# 03_-_28PINS_SCHEMATIC.net
KiCad netlist of a schematic drawn in Altium Designer
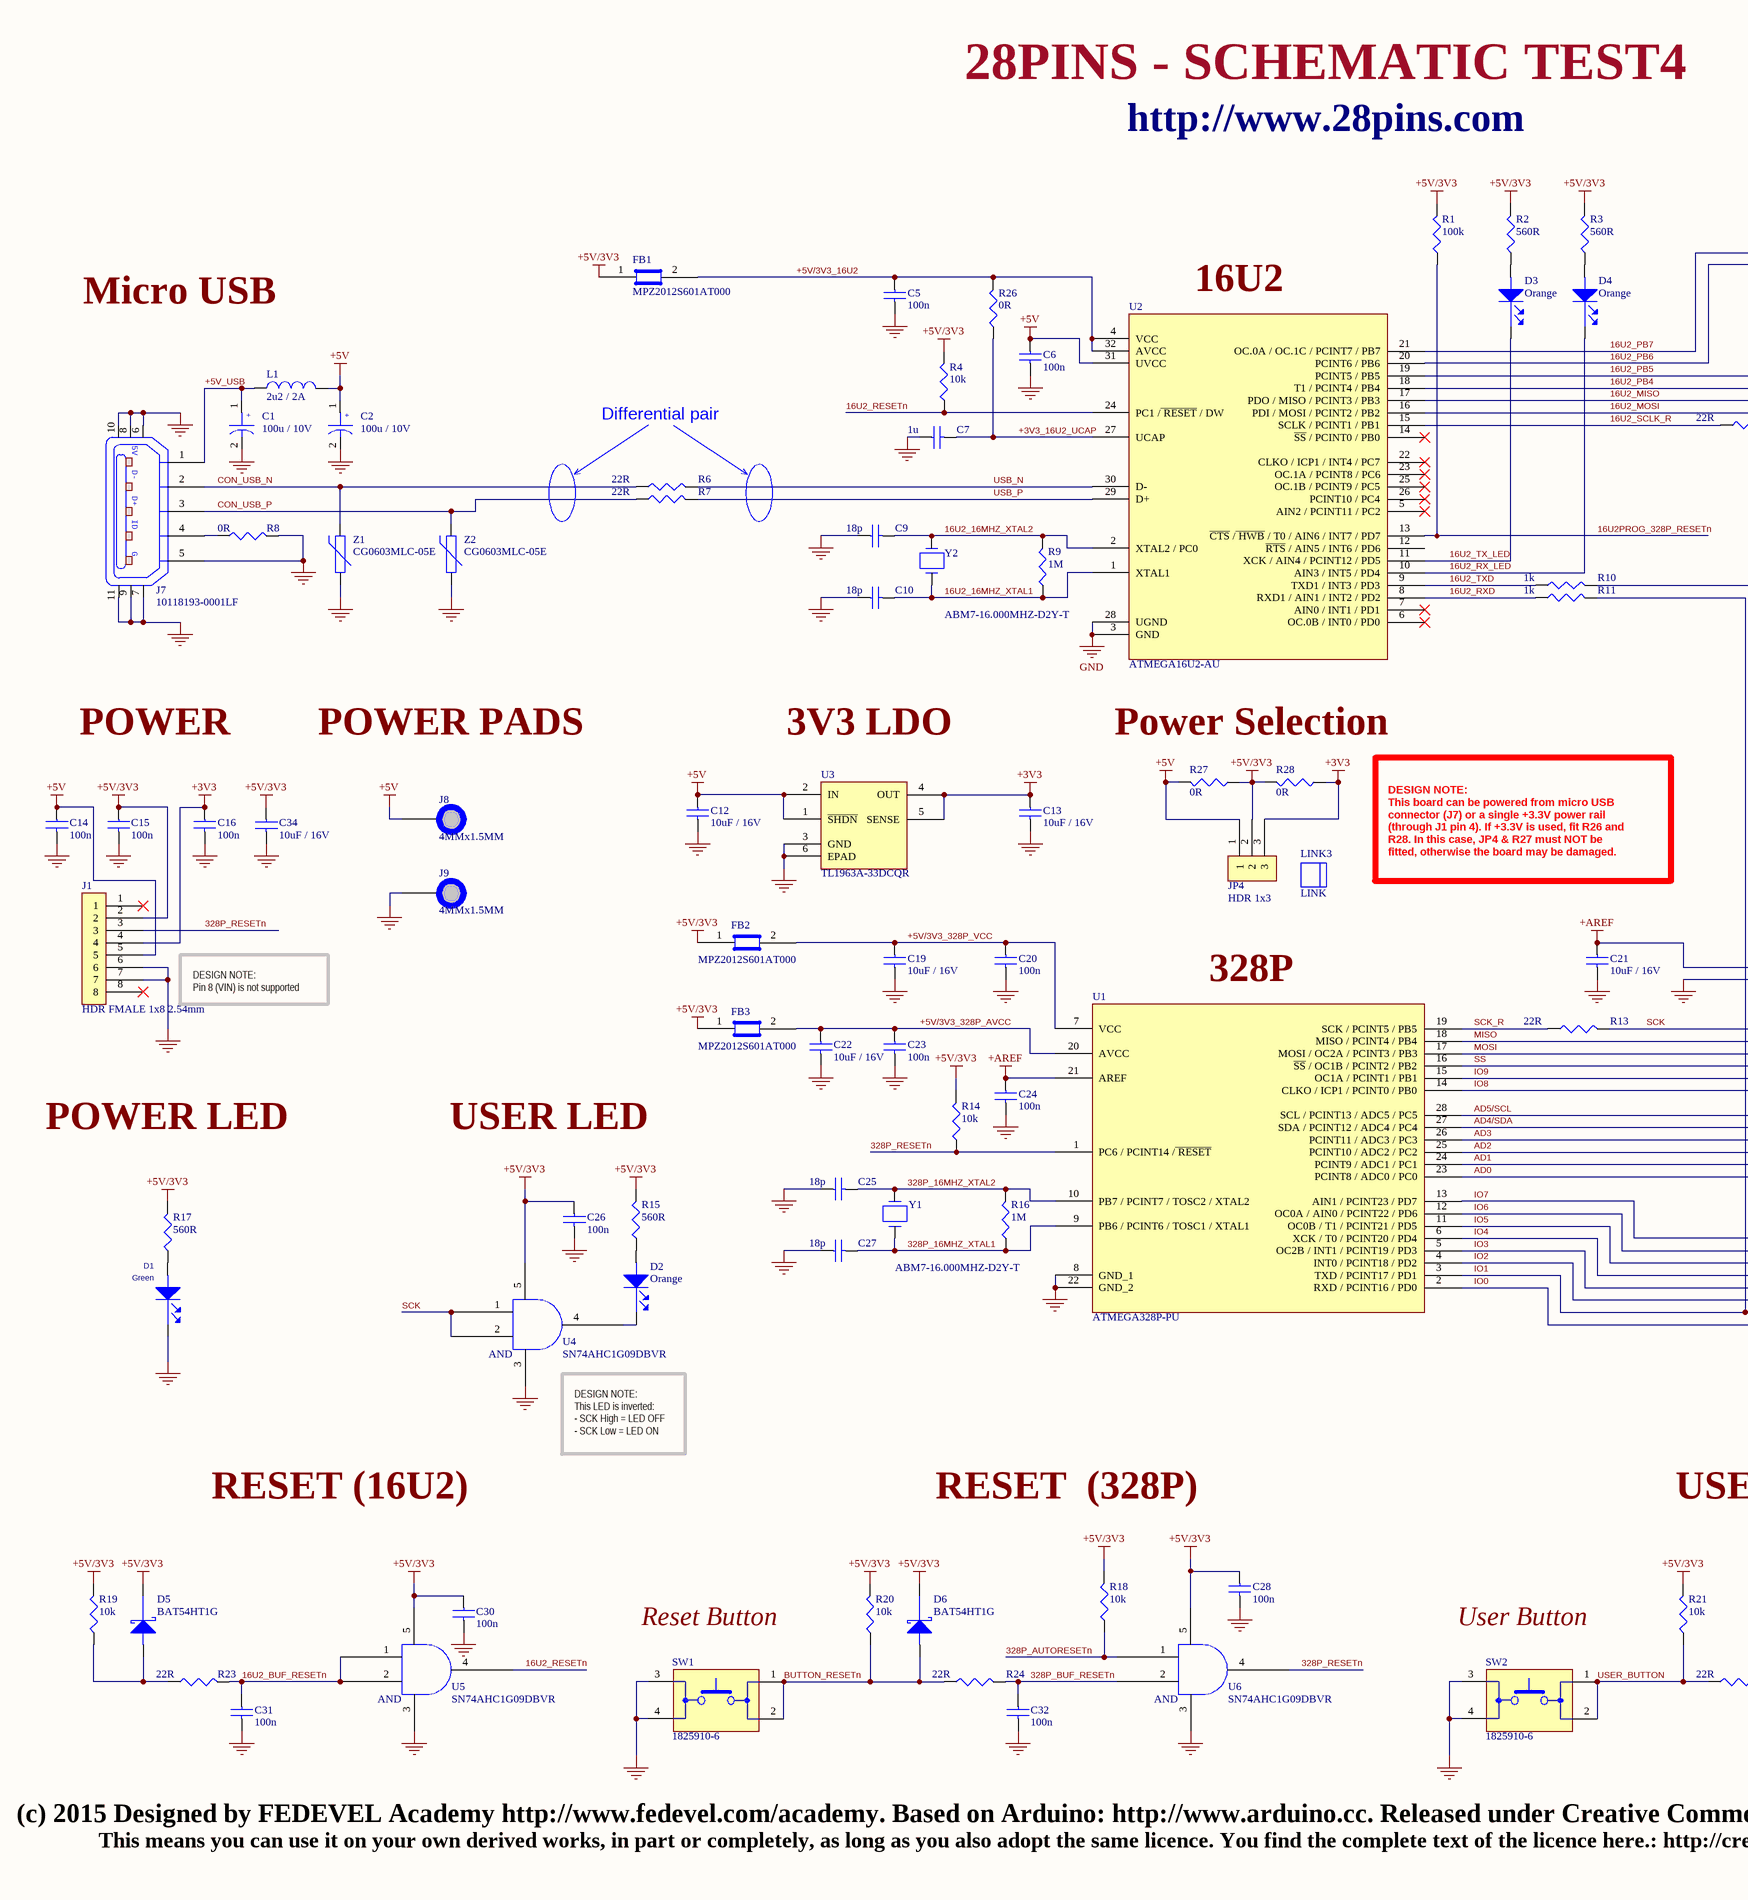
[diagram p0: [03] - 28PINS SCHEMATIC.SchDoc, left]
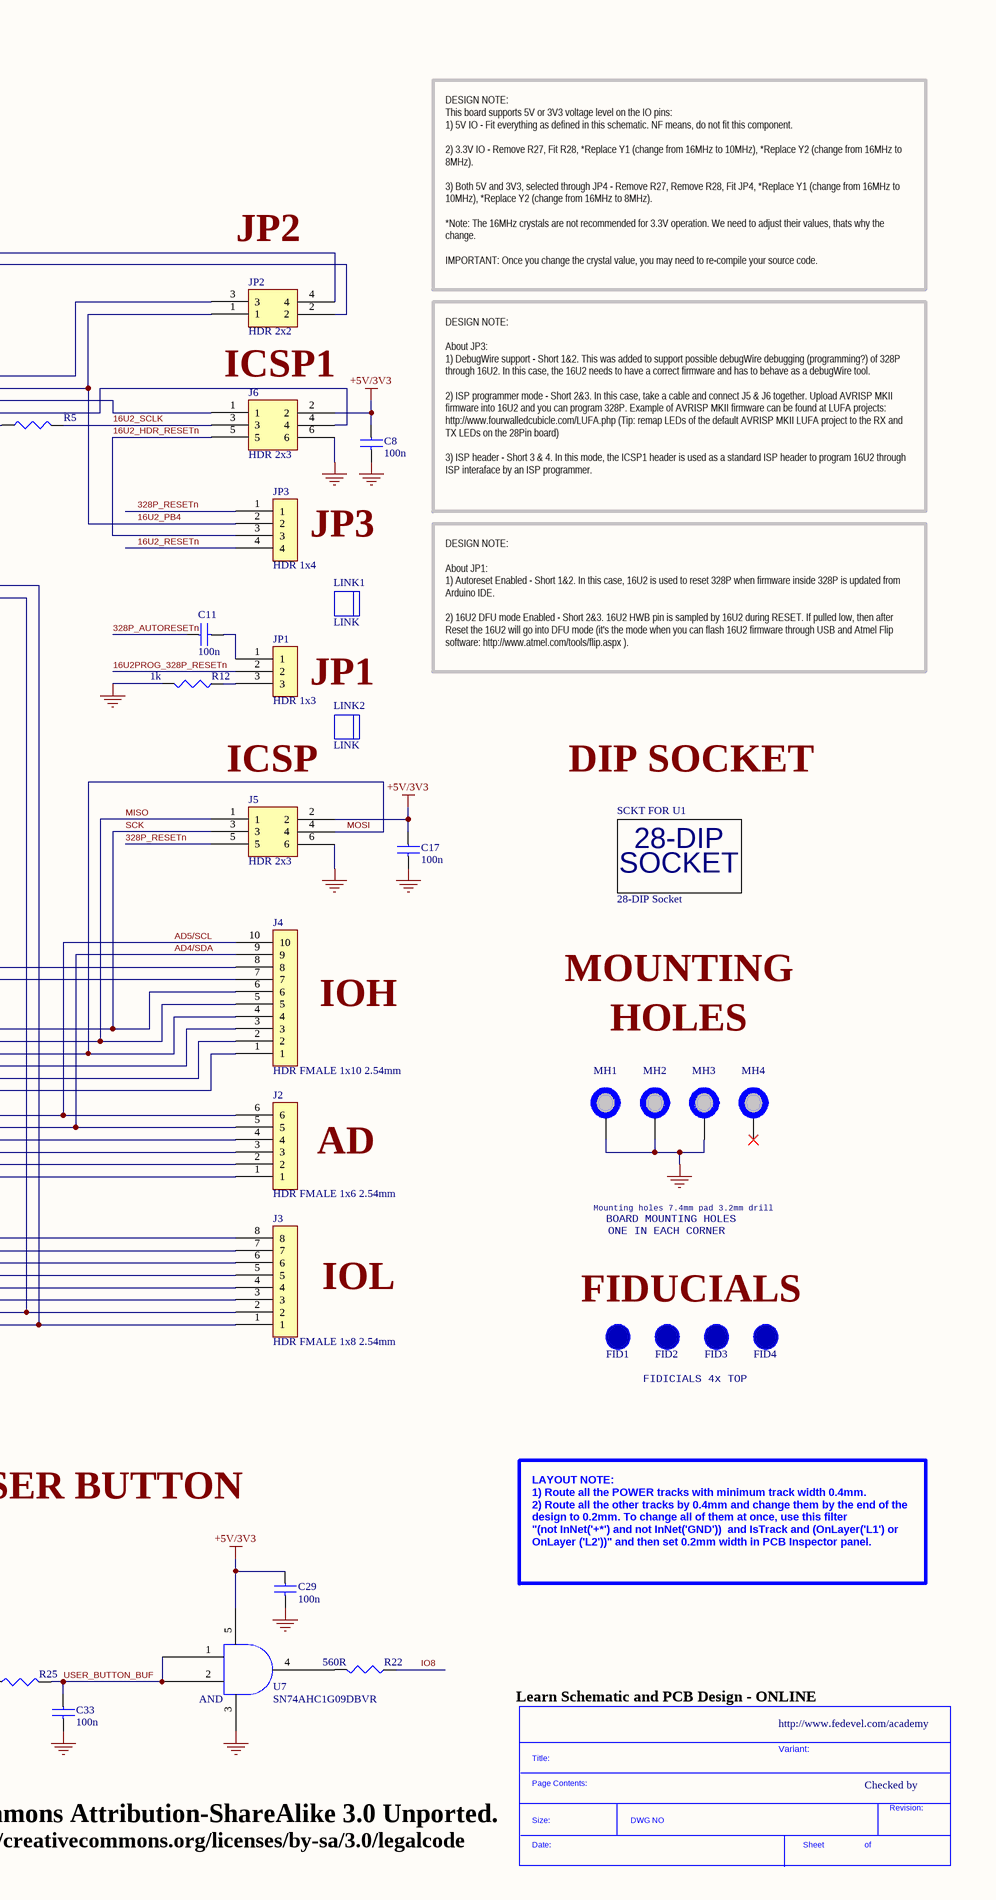
[diagram p1: [03] - 28PINS SCHEMATIC.SchDoc, right]

(export (version "E")
  (design (tool "Eeschema 10.0.6"))
  (components
    (comp (ref "*") (value "SDTitleBlock") (libsource (lib "*") (part "SDTitleBlock")))
    (comp (ref "C1")
      (value "100u / 10V")
      (footprint "C_ALU_C_SIZE")
      (description "CAP ALUM 100UF 10V 20% SMD")
      (fields
        (field (name "MANUFACTURER") "Panasonic Electronic Components")
        (field (name "MANUFACTURER PART NUMBER") "EEE-1AA101WR")
        (field (name ".CREATOR") "MM")
        (field (name ".CHECKED PCB") "RF")
        (field (name ".CHECKED SCH") "RF")
      )
      (libsource (lib "Integrated_Library_FEDEVEL_APR_2015") (part "EEE-1AA101WR"))
    )
    (comp (ref "C2")
      (value "100u / 10V")
      (footprint "C_ALU_C_SIZE")
      (description "CAP ALUM 100UF 10V 20% SMD")
      (fields
        (field (name "MANUFACTURER") "Panasonic Electronic Components")
        (field (name "MANUFACTURER PART NUMBER") "EEE-1AA101WR")
        (field (name ".CREATOR") "MM")
        (field (name ".CHECKED PCB") "RF")
        (field (name ".CHECKED SCH") "RF")
      )
      (libsource (lib "Integrated_Library_FEDEVEL_APR_2015") (part "EEE-1AA101WR"))
    )
    (comp (ref "C5")
      (value "100n")
      (footprint "C0805")
      (description "CAP CER 0.1UF 50V 10% X7R 0805")
      (fields
        (field (name "MANUFACTURER") "TDK Corporation")
        (field (name "MANUFACTURER PART NUMBER") "C2012X7R1H104K085AA")
        (field (name ".CREATOR") "MM")
        (field (name ".CHECKED PCB") "RF")
        (field (name ".CHECKED SCH") "RF")
      )
      (libsource (lib "Integrated_Library_FEDEVEL_APR_2015") (part "C2012X7R1H104K085AA"))
    )
    (comp (ref "C6")
      (value "100n")
      (footprint "C0805")
      (description "CAP CER 0.1UF 50V 10% X7R 0805")
      (fields
        (field (name "MANUFACTURER") "TDK Corporation")
        (field (name "MANUFACTURER PART NUMBER") "C2012X7R1H104K085AA")
        (field (name ".CREATOR") "MM")
        (field (name ".CHECKED PCB") "RF")
        (field (name ".CHECKED SCH") "RF")
      )
      (libsource (lib "Integrated_Library_FEDEVEL_APR_2015") (part "C2012X7R1H104K085AA"))
    )
    (comp (ref "C7")
      (value "1u")
      (footprint "C0805")
      (description "CAP CER 1UF 25V 10% X5R 0805")
      (fields
        (field (name "MANUFACTURER") "TDK Corporation")
        (field (name "MANUFACTURER PART NUMBER") "C2012X5R1E105K125AA")
        (field (name ".CREATOR") "MM")
        (field (name ".CHECKED PCB") "RF")
        (field (name ".CHECKED SCH") "RF")
      )
      (libsource (lib "Integrated_Library_FEDEVEL_APR_2015") (part "C2012X5R1E105K125AA"))
    )
    (comp (ref "C8")
      (value "100n")
      (footprint "C0805")
      (description "CAP CER 0.1UF 50V 10% X7R 0805")
      (fields
        (field (name "MANUFACTURER") "TDK Corporation")
        (field (name "MANUFACTURER PART NUMBER") "C2012X7R1H104K085AA")
        (field (name ".CREATOR") "MM")
        (field (name ".CHECKED PCB") "RF")
        (field (name ".CHECKED SCH") "RF")
      )
      (libsource (lib "Integrated_Library_FEDEVEL_APR_2015") (part "C2012X7R1H104K085AA"))
    )
    (comp (ref "C9")
      (value "18p")
      (footprint "C0805")
      (description "CAP CER 18PF 50V 5% NP0 0805")
      (fields
        (field (name "MANUFACTURER") "Kemet")
        (field (name "MANUFACTURER PART NUMBER") "C0805C180J5GACTU")
        (field (name ".CREATOR") "MM")
        (field (name ".CHECKED PCB") "RF")
        (field (name ".CHECKED SCH") "RF")
      )
      (libsource (lib "Integrated_Library_FEDEVEL_APR_2015") (part "C0805C180J5GACTU"))
    )
    (comp (ref "C10")
      (value "18p")
      (footprint "C0805")
      (description "CAP CER 18PF 50V 5% NP0 0805")
      (fields
        (field (name "MANUFACTURER") "Kemet")
        (field (name "MANUFACTURER PART NUMBER") "C0805C180J5GACTU")
        (field (name ".CREATOR") "MM")
        (field (name ".CHECKED PCB") "RF")
        (field (name ".CHECKED SCH") "RF")
      )
      (libsource (lib "Integrated_Library_FEDEVEL_APR_2015") (part "C0805C180J5GACTU"))
    )
    (comp (ref "C11")
      (value "100n")
      (footprint "C0805")
      (description "CAP CER 0.1UF 50V 10% X7R 0805")
      (fields
        (field (name "MANUFACTURER") "TDK Corporation")
        (field (name "MANUFACTURER PART NUMBER") "C2012X7R1H104K085AA")
        (field (name ".CREATOR") "MM")
        (field (name ".CHECKED PCB") "RF")
        (field (name ".CHECKED SCH") "RF")
      )
      (libsource (lib "Integrated_Library_FEDEVEL_APR_2015") (part "C2012X7R1H104K085AA"))
    )
    (comp (ref "C12")
      (value "10uF / 16V")
      (footprint "C0805")
      (description "CAP CER 10UF 16V 20% X5R 0805")
      (fields
        (field (name "MANUFACTURER") "TDK Corporation")
        (field (name "MANUFACTURER PART NUMBER") "C2012X5R1C106M/1.25")
      )
      (libsource (lib "Integrated_Library_FEDEVEL_APR_2015") (part "C2012X5R1C106M"))
    )
    (comp (ref "C13")
      (value "10uF / 16V")
      (footprint "C0805")
      (description "CAP CER 10UF 16V 20% X5R 0805")
      (fields
        (field (name "MANUFACTURER") "TDK Corporation")
        (field (name "MANUFACTURER PART NUMBER") "C2012X5R1C106M/1.25")
      )
      (libsource (lib "Integrated_Library_FEDEVEL_APR_2015") (part "C2012X5R1C106M"))
    )
    (comp (ref "C14")
      (value "100n")
      (footprint "C0805")
      (description "CAP CER 0.1UF 50V 10% X7R 0805")
      (fields
        (field (name "MANUFACTURER") "TDK Corporation")
        (field (name "MANUFACTURER PART NUMBER") "C2012X7R1H104K085AA")
        (field (name ".CREATOR") "MM")
        (field (name ".CHECKED PCB") "RF")
        (field (name ".CHECKED SCH") "RF")
      )
      (libsource (lib "Integrated_Library_FEDEVEL_APR_2015") (part "C2012X7R1H104K085AA"))
    )
    (comp (ref "C15")
      (value "100n")
      (footprint "C0805")
      (description "CAP CER 0.1UF 50V 10% X7R 0805")
      (fields
        (field (name "MANUFACTURER") "TDK Corporation")
        (field (name "MANUFACTURER PART NUMBER") "C2012X7R1H104K085AA")
        (field (name ".CREATOR") "MM")
        (field (name ".CHECKED PCB") "RF")
        (field (name ".CHECKED SCH") "RF")
      )
      (libsource (lib "Integrated_Library_FEDEVEL_APR_2015") (part "C2012X7R1H104K085AA"))
    )
    (comp (ref "C16")
      (value "100n")
      (footprint "C0805")
      (description "CAP CER 0.1UF 50V 10% X7R 0805")
      (fields
        (field (name "MANUFACTURER") "TDK Corporation")
        (field (name "MANUFACTURER PART NUMBER") "C2012X7R1H104K085AA")
        (field (name ".CREATOR") "MM")
        (field (name ".CHECKED PCB") "RF")
        (field (name ".CHECKED SCH") "RF")
      )
      (libsource (lib "Integrated_Library_FEDEVEL_APR_2015") (part "C2012X7R1H104K085AA"))
    )
    (comp (ref "C17")
      (value "100n")
      (footprint "C0805")
      (description "CAP CER 0.1UF 50V 10% X7R 0805")
      (fields
        (field (name "MANUFACTURER") "TDK Corporation")
        (field (name "MANUFACTURER PART NUMBER") "C2012X7R1H104K085AA")
        (field (name ".CREATOR") "MM")
        (field (name ".CHECKED PCB") "RF")
        (field (name ".CHECKED SCH") "RF")
      )
      (libsource (lib "Integrated_Library_FEDEVEL_APR_2015") (part "C2012X7R1H104K085AA"))
    )
    (comp (ref "C19")
      (value "10uF / 16V")
      (footprint "C0805")
      (description "CAP CER 10UF 16V 20% X5R 0805")
      (fields
        (field (name "MANUFACTURER") "TDK Corporation")
        (field (name "MANUFACTURER PART NUMBER") "C2012X5R1C106M/1.25")
      )
      (libsource (lib "Integrated_Library_FEDEVEL_APR_2015") (part "C2012X5R1C106M"))
    )
    (comp (ref "C20")
      (value "100n")
      (footprint "C0805")
      (description "CAP CER 0.1UF 50V 10% X7R 0805")
      (fields
        (field (name "MANUFACTURER") "TDK Corporation")
        (field (name "MANUFACTURER PART NUMBER") "C2012X7R1H104K085AA")
        (field (name ".CREATOR") "MM")
        (field (name ".CHECKED PCB") "RF")
        (field (name ".CHECKED SCH") "RF")
      )
      (libsource (lib "Integrated_Library_FEDEVEL_APR_2015") (part "C2012X7R1H104K085AA"))
    )
    (comp (ref "C21")
      (value "10uF / 16V")
      (footprint "C0805")
      (description "CAP CER 10UF 16V 20% X5R 0805")
      (fields
        (field (name "MANUFACTURER") "TDK Corporation")
        (field (name "MANUFACTURER PART NUMBER") "C2012X5R1C106M/1.25")
      )
      (libsource (lib "Integrated_Library_FEDEVEL_APR_2015") (part "C2012X5R1C106M"))
    )
    (comp (ref "C22")
      (value "10uF / 16V")
      (footprint "C0805")
      (description "CAP CER 10UF 16V 20% X5R 0805")
      (fields
        (field (name "MANUFACTURER") "TDK Corporation")
        (field (name "MANUFACTURER PART NUMBER") "C2012X5R1C106M/1.25")
      )
      (libsource (lib "Integrated_Library_FEDEVEL_APR_2015") (part "C2012X5R1C106M"))
    )
    (comp (ref "C23")
      (value "100n")
      (footprint "C0805")
      (description "CAP CER 0.1UF 50V 10% X7R 0805")
      (fields
        (field (name "MANUFACTURER") "TDK Corporation")
        (field (name "MANUFACTURER PART NUMBER") "C2012X7R1H104K085AA")
        (field (name ".CREATOR") "MM")
        (field (name ".CHECKED PCB") "RF")
        (field (name ".CHECKED SCH") "RF")
      )
      (libsource (lib "Integrated_Library_FEDEVEL_APR_2015") (part "C2012X7R1H104K085AA"))
    )
    (comp (ref "C24")
      (value "100n")
      (footprint "C0805")
      (description "CAP CER 0.1UF 50V 10% X7R 0805")
      (fields
        (field (name "MANUFACTURER") "TDK Corporation")
        (field (name "MANUFACTURER PART NUMBER") "C2012X7R1H104K085AA")
        (field (name ".CREATOR") "MM")
        (field (name ".CHECKED PCB") "RF")
        (field (name ".CHECKED SCH") "RF")
      )
      (libsource (lib "Integrated_Library_FEDEVEL_APR_2015") (part "C2012X7R1H104K085AA"))
    )
    (comp (ref "C25")
      (value "18p")
      (footprint "C0805")
      (description "CAP CER 18PF 50V 5% NP0 0805")
      (fields
        (field (name "MANUFACTURER") "Kemet")
        (field (name "MANUFACTURER PART NUMBER") "C0805C180J5GACTU")
        (field (name ".CREATOR") "MM")
        (field (name ".CHECKED PCB") "RF")
        (field (name ".CHECKED SCH") "RF")
      )
      (libsource (lib "Integrated_Library_FEDEVEL_APR_2015") (part "C0805C180J5GACTU"))
    )
    (comp (ref "C26")
      (value "100n")
      (footprint "C0805")
      (description "CAP CER 0.1UF 50V 10% X7R 0805")
      (fields
        (field (name "MANUFACTURER") "TDK Corporation")
        (field (name "MANUFACTURER PART NUMBER") "C2012X7R1H104K085AA")
        (field (name ".CREATOR") "MM")
        (field (name ".CHECKED PCB") "RF")
        (field (name ".CHECKED SCH") "RF")
      )
      (libsource (lib "Integrated_Library_FEDEVEL_APR_2015") (part "C2012X7R1H104K085AA"))
    )
    (comp (ref "C27")
      (value "18p")
      (footprint "C0805")
      (description "CAP CER 18PF 50V 5% NP0 0805")
      (fields
        (field (name "MANUFACTURER") "Kemet")
        (field (name "MANUFACTURER PART NUMBER") "C0805C180J5GACTU")
        (field (name ".CREATOR") "MM")
        (field (name ".CHECKED PCB") "RF")
        (field (name ".CHECKED SCH") "RF")
      )
      (libsource (lib "Integrated_Library_FEDEVEL_APR_2015") (part "C0805C180J5GACTU"))
    )
    (comp (ref "C28")
      (value "100n")
      (footprint "C0805")
      (description "CAP CER 0.1UF 50V 10% X7R 0805")
      (fields
        (field (name "MANUFACTURER") "TDK Corporation")
        (field (name "MANUFACTURER PART NUMBER") "C2012X7R1H104K085AA")
        (field (name ".CREATOR") "MM")
        (field (name ".CHECKED PCB") "RF")
        (field (name ".CHECKED SCH") "RF")
      )
      (libsource (lib "Integrated_Library_FEDEVEL_APR_2015") (part "C2012X7R1H104K085AA"))
    )
    (comp (ref "C29")
      (value "100n")
      (footprint "C0805")
      (description "CAP CER 0.1UF 50V 10% X7R 0805")
      (fields
        (field (name "MANUFACTURER") "TDK Corporation")
        (field (name "MANUFACTURER PART NUMBER") "C2012X7R1H104K085AA")
        (field (name ".CREATOR") "MM")
        (field (name ".CHECKED PCB") "RF")
        (field (name ".CHECKED SCH") "RF")
      )
      (libsource (lib "Integrated_Library_FEDEVEL_APR_2015") (part "C2012X7R1H104K085AA"))
    )
    (comp (ref "C30")
      (value "100n")
      (footprint "C0805")
      (description "CAP CER 0.1UF 50V 10% X7R 0805")
      (fields
        (field (name "MANUFACTURER") "TDK Corporation")
        (field (name "MANUFACTURER PART NUMBER") "C2012X7R1H104K085AA")
        (field (name ".CREATOR") "MM")
        (field (name ".CHECKED PCB") "RF")
        (field (name ".CHECKED SCH") "RF")
      )
      (libsource (lib "Integrated_Library_FEDEVEL_APR_2015") (part "C2012X7R1H104K085AA"))
    )
    (comp (ref "C31")
      (value "100n")
      (footprint "C0805")
      (description "CAP CER 0.1UF 50V 10% X7R 0805")
      (fields
        (field (name "MANUFACTURER") "TDK Corporation")
        (field (name "MANUFACTURER PART NUMBER") "C2012X7R1H104K085AA")
        (field (name ".CREATOR") "MM")
        (field (name ".CHECKED PCB") "RF")
        (field (name ".CHECKED SCH") "RF")
      )
      (libsource (lib "Integrated_Library_FEDEVEL_APR_2015") (part "C2012X7R1H104K085AA"))
    )
    (comp (ref "C32")
      (value "100n")
      (footprint "C0805")
      (description "CAP CER 0.1UF 50V 10% X7R 0805")
      (fields
        (field (name "MANUFACTURER") "TDK Corporation")
        (field (name "MANUFACTURER PART NUMBER") "C2012X7R1H104K085AA")
        (field (name ".CREATOR") "MM")
        (field (name ".CHECKED PCB") "RF")
        (field (name ".CHECKED SCH") "RF")
      )
      (libsource (lib "Integrated_Library_FEDEVEL_APR_2015") (part "C2012X7R1H104K085AA"))
    )
    (comp (ref "C33")
      (value "100n")
      (footprint "C0805")
      (description "CAP CER 0.1UF 50V 10% X7R 0805")
      (fields
        (field (name "MANUFACTURER") "TDK Corporation")
        (field (name "MANUFACTURER PART NUMBER") "C2012X7R1H104K085AA")
        (field (name ".CREATOR") "MM")
        (field (name ".CHECKED PCB") "RF")
        (field (name ".CHECKED SCH") "RF")
      )
      (libsource (lib "Integrated_Library_FEDEVEL_APR_2015") (part "C2012X7R1H104K085AA"))
    )
    (comp (ref "C34")
      (value "10uF / 16V")
      (footprint "C0805")
      (description "CAP CER 10UF 16V 20% X5R 0805")
      (fields
        (field (name "MANUFACTURER") "TDK Corporation")
        (field (name "MANUFACTURER PART NUMBER") "C2012X5R1C106M/1.25")
      )
      (libsource (lib "Integrated_Library_FEDEVEL_APR_2015") (part "C2012X5R1C106M"))
    )
    (comp (ref "D1")
      (value "Green")
      (footprint "LED_0603")
      (description "LED SMARTLED GREEN 570NM 0603")
      (fields
        (field (name "MANUFACTURER") "OSRAM Opto Semiconductors Inc")
        (field (name "MANUFACTURER PART NUMBER") "LG L29K-G2J1-24-Z")
      )
      (libsource (lib "Integrated_Library_FEDEVEL_APR_2015") (part "LG L29K-G2J1-24-Z"))
    )
    (comp (ref "D2")
      (value "Orange")
      (footprint "LED_0603")
      (description "LED SMARTLED ORANGE 606NM 0603")
      (fields
        (field (name "MANUFACTURER") "OSRAM Opto Semiconductors Inc")
        (field (name "MANUFACTURER PART NUMBER") "LO L29K-H2K1-24-Z")
      )
      (libsource (lib "Integrated_Library_FEDEVEL_APR_2015") (part "LO L29K-H2K1-24-Z"))
    )
    (comp (ref "D3")
      (value "Orange")
      (footprint "LED_0603")
      (description "LED SMARTLED ORANGE 606NM 0603")
      (fields
        (field (name "MANUFACTURER") "OSRAM Opto Semiconductors Inc")
        (field (name "MANUFACTURER PART NUMBER") "LO L29K-H2K1-24-Z")
      )
      (libsource (lib "Integrated_Library_FEDEVEL_APR_2015") (part "LO L29K-H2K1-24-Z"))
    )
    (comp (ref "D4")
      (value "Orange")
      (footprint "LED_0603")
      (description "LED SMARTLED ORANGE 606NM 0603")
      (fields
        (field (name "MANUFACTURER") "OSRAM Opto Semiconductors Inc")
        (field (name "MANUFACTURER PART NUMBER") "LO L29K-H2K1-24-Z")
      )
      (libsource (lib "Integrated_Library_FEDEVEL_APR_2015") (part "LO L29K-H2K1-24-Z"))
    )
    (comp (ref "D5")
      (value "BAT54HT1G")
      (footprint "SOD323")
      (description "DIODE SCHOTTKY 30V 0.2A SOD323")
      (fields (field (name "MANUFACTURER") "Fairchild Semiconductor") (field (name ".CREATOR") "MM"))
      (libsource (lib "Integrated_Library_FEDEVEL_APR_2015") (part "BAT54HT1G"))
    )
    (comp (ref "D6")
      (value "BAT54HT1G")
      (footprint "SOD323")
      (description "DIODE SCHOTTKY 30V 0.2A SOD323")
      (fields (field (name "MANUFACTURER") "Fairchild Semiconductor") (field (name ".CREATOR") "MM"))
      (libsource (lib "Integrated_Library_FEDEVEL_APR_2015") (part "BAT54HT1G"))
    )
    (comp (ref "FB1")
      (value "MPZ2012S601AT000")
      (footprint "C0805")
      (description "FERRITE CHIP BEAD 600 OHM SMD")
      (fields
        (field (name "MANUFACTURER") "TDK Corporation")
        (field (name ".CREATOR") "MM")
        (field (name ".CHECKED PCB") "RF")
        (field (name ".CHECKED SCH") "RF")
      )
      (libsource (lib "Integrated_Library_FEDEVEL_APR_2015") (part "MPZ2012S601AT000"))
    )
    (comp (ref "FB2")
      (value "MPZ2012S601AT000")
      (footprint "C0805")
      (description "FERRITE CHIP BEAD 600 OHM SMD")
      (fields
        (field (name "MANUFACTURER") "TDK Corporation")
        (field (name ".CREATOR") "MM")
        (field (name ".CHECKED PCB") "RF")
        (field (name ".CHECKED SCH") "RF")
      )
      (libsource (lib "Integrated_Library_FEDEVEL_APR_2015") (part "MPZ2012S601AT000"))
    )
    (comp (ref "FB3")
      (value "MPZ2012S601AT000")
      (footprint "C0805")
      (description "FERRITE CHIP BEAD 600 OHM SMD")
      (fields
        (field (name "MANUFACTURER") "TDK Corporation")
        (field (name ".CREATOR") "MM")
        (field (name ".CHECKED PCB") "RF")
        (field (name ".CHECKED SCH") "RF")
      )
      (libsource (lib "Integrated_Library_FEDEVEL_APR_2015") (part "MPZ2012S601AT000"))
    )
    (comp (ref "FID1")
      (value "FID_1MMC")
      (footprint "FID_40X120D")
      (description "Fiducial 40mil Diameter, 120mil Mask")
      (libsource (lib "Integrated_Library_FEDEVEL_APR_2015") (part "FID_1MMC"))
    )
    (comp (ref "FID2")
      (value "FID_1MMC")
      (footprint "FID_40X120D")
      (description "Fiducial 40mil Diameter, 120mil Mask")
      (libsource (lib "Integrated_Library_FEDEVEL_APR_2015") (part "FID_1MMC"))
    )
    (comp (ref "FID3")
      (value "FID_1MMC")
      (footprint "FID_40X120D")
      (description "Fiducial 40mil Diameter, 120mil Mask")
      (libsource (lib "Integrated_Library_FEDEVEL_APR_2015") (part "FID_1MMC"))
    )
    (comp (ref "FID4")
      (value "FID_1MMC")
      (footprint "FID_40X120D")
      (description "Fiducial 40mil Diameter, 120mil Mask")
      (libsource (lib "Integrated_Library_FEDEVEL_APR_2015") (part "FID_1MMC"))
    )
    (comp (ref "J1")
      (value "HDR FMALE 1x8 2.54mm")
      (footprint "Hdr_Female_1x8_2.54mm")
      (description "08-WAY SIL VERT SOCKET L/FREE")
      (fields
        (field (name "MANUFACTURER") "Harwin Inc")
        (field (name "MANUFACTURER PART NUMBER") "M20-7820842")
        (field (name ".CREATOR") "MM")
        (field (name ".CHECKED PCB") "RF")
        (field (name ".CHECKED SCH") "RF")
      )
      (libsource (lib "Integrated_Library_FEDEVEL_APR_2015") (part "M20-7820842"))
    )
    (comp (ref "J2")
      (value "HDR FMALE 1x6 2.54mm")
      (footprint "Hdr_Female_1x6_2.54mm")
      (description "06-WAY SIL VERT SOCKET L/FREE")
      (fields
        (field (name "MANUFACTURER") "Harwin Inc")
        (field (name "MANUFACTURER PART NUMBER") "M20-7820646")
        (field (name ".CHECKED PCB") "MM")
        (field (name ".CHECKED SCH") "MM")
        (field (name ".CREATOR") "MM")
      )
      (libsource (lib "Integrated_Library_FEDEVEL_APR_2015") (part "M20-7820646"))
    )
    (comp (ref "J3")
      (value "HDR FMALE 1x8 2.54mm")
      (footprint "Hdr_Female_1x8_2.54mm")
      (description "08-WAY SIL VERT SOCKET L/FREE")
      (fields
        (field (name "MANUFACTURER") "Harwin Inc")
        (field (name "MANUFACTURER PART NUMBER") "M20-7820842")
        (field (name ".CREATOR") "MM")
        (field (name ".CHECKED PCB") "RF")
        (field (name ".CHECKED SCH") "RF")
      )
      (libsource (lib "") (part "M20-7820842_1"))
    )
    (comp (ref "J4")
      (value "HDR FMALE 1x10 2.54mm")
      (footprint "Hdr_Female_1x10_2.54mm")
      (description "10-WAY SIL VERT SOCKET L/FREE")
      (fields
        (field (name "MANUFACTURER") "Harwin Inc")
        (field (name "MANUFACTURER PART NUMBER") "M20-7821046")
        (field (name ".CREATOR") "MM")
        (field (name ".CHECKED PCB") "RF")
        (field (name ".CHECKED SCH") "RF")
      )
      (libsource (lib "Integrated_Library_FEDEVEL_APR_2015") (part "M20-7821046"))
    )
    (comp (ref "J5")
      (value "HDR 2x3")
      (footprint "HDR_2x3_2.54MM")
      (description "CONN HEADER 6POS .100 STR 30AU")
      (fields
        (field (name "MANUFACTURER") "FCI")
        (field (name "MANUFACTURER PART NUMBER") "67997-106HLF")
        (field (name ".CREATOR") "MM")
        (field (name ".CHECKED PCB") "RF")
        (field (name ".CHECKED SCH") "RF")
      )
      (libsource (lib "Integrated_Library_FEDEVEL_APR_2015") (part "67997-106HLF"))
    )
    (comp (ref "J6")
      (value "HDR 2x3")
      (footprint "HDR_2x3_2.54MM")
      (description "CONN HEADER 6POS .100 STR 30AU")
      (fields
        (field (name "MANUFACTURER") "FCI")
        (field (name "MANUFACTURER PART NUMBER") "67997-106HLF")
        (field (name ".CREATOR") "MM")
        (field (name ".CHECKED PCB") "RF")
        (field (name ".CHECKED SCH") "RF")
      )
      (libsource (lib "Integrated_Library_FEDEVEL_APR_2015") (part "67997-106HLF"))
    )
    (comp (ref "J7")
      (value "10118193-0001LF")
      (footprint "10118193")
      (description "CONN USB MICRO B RECPT SMT R/A")
      (fields
        (field (name "MANUFACTURER") "FCI")
        (field (name ".CREATOR") "MM")
        (field (name ".CHECKED PCB") "RF")
        (field (name ".CHECKED SCH") "MM")
      )
      (libsource (lib "Integrated_Library_FEDEVEL_APR_2015") (part "10118193-0001LF"))
    )
    (comp (ref "J8")
      (value "4MMx1.5MM")
      (footprint "PAD_WITH_HOLE_4MMx1.5MM")
      (description "Pad with a hole 4mm x 1.5mm")
      (libsource (lib "Integrated_Library_FEDEVEL_APR_2015") (part "PAD_WITH_HOLE_4MMx1.5MM"))
    )
    (comp (ref "J9")
      (value "4MMx1.5MM")
      (footprint "PAD_WITH_HOLE_4MMx1.5MM")
      (description "Pad with a hole 4mm x 1.5mm")
      (libsource (lib "Integrated_Library_FEDEVEL_APR_2015") (part "PAD_WITH_HOLE_4MMx1.5MM"))
    )
    (comp (ref "JP1")
      (value "HDR 1x3")
      (footprint "Hdr_1x3_2.54mm")
      (description "BERGSTIK II .100\" SR STRAIGHT")
      (fields
        (field (name "MANUFACTURER") "FCI")
        (field (name "MANUFACTURER PART NUMBER") "68000-103HLF")
        (field (name ".CREATOR") "MM")
      )
      (libsource (lib "") (part "68000-103HLF_1"))
    )
    (comp (ref "JP2")
      (value "HDR 2x2")
      (footprint "HDR_2x2_2.54MM")
      (description "CONN HEADER 4POS .100 STR 15AU")
      (fields
        (field (name "MANUFACTURER") "FCI")
        (field (name "MANUFACTURER PART NUMBER") "68602-204HLF")
        (field (name ".CREATOR") "MM")
        (field (name ".CHECKED PCB") "RF")
        (field (name ".CHECKED SCH") "RF")
      )
      (libsource (lib "Integrated_Library_FEDEVEL_APR_2015") (part "68602-204HLF"))
    )
    (comp (ref "JP3")
      (value "HDR 1x4")
      (footprint "HDR_1x4_2.54MM")
      (description "CONN HEADER 4POS .100 STR 15AU")
      (fields
        (field (name "MANUFACTURER") "FCI")
        (field (name "MANUFACTURER PART NUMBER") "68001-204HLF")
        (field (name ".CHECKED PCB") "RF")
        (field (name ".CHECKED SCH") "RF")
      )
      (libsource (lib "Integrated_Library_FEDEVEL_APR_2015") (part "68001-204HLF"))
    )
    (comp (ref "JP4")
      (value "HDR 1x3")
      (footprint "Hdr_1x3_2.54mm")
      (description "BERGSTIK II .100\" SR STRAIGHT")
      (fields
        (field (name "MANUFACTURER") "FCI")
        (field (name "MANUFACTURER PART NUMBER") "68000-103HLF")
        (field (name ".CREATOR") "MM")
      )
      (libsource (lib "Integrated_Library_FEDEVEL_APR_2015") (part "68000-103HLF"))
    )
    (comp (ref "L1")
      (value "2u2 / 2A")
      (footprint "C1210_IND")
      (description "FIXED IND 2.2UH 2A 80 MOHM SMD")
      (fields
        (field (name "MANUFACTURER") "Kemet")
        (field (name "MANUFACTURER PART NUMBER") "L1210R2R2MDWIT")
        (field (name ".CREATOR") "MM")
        (field (name ".CHECKED PCB") "RF")
        (field (name ".CHECKED SCH") "RF")
      )
      (libsource (lib "Integrated_Library_FEDEVEL_APR_2015") (part "L1210R2R2MDWIT"))
    )
    (comp (ref "LINK1")
      (value "LINK")
      (description "CONN JUMPER SHORTING .100\" GOLD")
      (fields
        (field (name "MANUFACTURER") "Sullins Connector Solutions")
        (field (name "MANUFACTURER PART NUMBER") "QPC02SXGN-RC")
      )
      (libsource (lib "Integrated_Library_FEDEVEL_APR_2015") (part "QPC02SXGN-RC"))
    )
    (comp (ref "LINK2")
      (value "LINK")
      (description "CONN JUMPER SHORTING .100\" GOLD")
      (fields
        (field (name "MANUFACTURER") "Sullins Connector Solutions")
        (field (name "MANUFACTURER PART NUMBER") "QPC02SXGN-RC")
      )
      (libsource (lib "Integrated_Library_FEDEVEL_APR_2015") (part "QPC02SXGN-RC"))
    )
    (comp (ref "LINK3")
      (value "LINK")
      (description "CONN JUMPER SHORTING .100\" GOLD")
      (fields
        (field (name "MANUFACTURER") "Sullins Connector Solutions")
        (field (name "MANUFACTURER PART NUMBER") "QPC02SXGN-RC")
      )
      (libsource (lib "Integrated_Library_FEDEVEL_APR_2015") (part "QPC02SXGN-RC"))
    )
    (comp (ref "MH1")
      (value "MH_7.4MMC_3.2MMD")
      (footprint "MH_7.4MMD_3.2MMD")
      (description "Mounting Hole 7.4mm Diameter, 3.2mm Drill")
      (fields (field (name ".CREATOR") "MM"))
      (libsource (lib "Integrated_Library_FEDEVEL_APR_2015") (part "MH_7.4MMC_3.2MMD"))
    )
    (comp (ref "MH2")
      (value "MH_7.4MMC_3.2MMD")
      (footprint "MH_7.4MMD_3.2MMD")
      (description "Mounting Hole 7.4mm Diameter, 3.2mm Drill")
      (fields (field (name ".CREATOR") "MM"))
      (libsource (lib "Integrated_Library_FEDEVEL_APR_2015") (part "MH_7.4MMC_3.2MMD"))
    )
    (comp (ref "MH3")
      (value "MH_7.4MMC_3.2MMD")
      (footprint "MH_7.4MMD_3.2MMD")
      (description "Mounting Hole 7.4mm Diameter, 3.2mm Drill")
      (fields (field (name ".CREATOR") "MM"))
      (libsource (lib "Integrated_Library_FEDEVEL_APR_2015") (part "MH_7.4MMC_3.2MMD"))
    )
    (comp (ref "MH4")
      (value "MH_7.4MMNC_3.2MMD")
      (footprint "MH_7.4MMD_3.2MMD_NON_COPPER_NPTH")
      (description "Mounting Hole 7.4mm Diameter (Non Copper), 3.2mm Drill NPTH")
      (libsource (lib "Integrated_Library_FEDEVEL_APR_2015") (part "MH_7.4MMNC_3.2MMD"))
    )
    (comp (ref "R1")
      (value "100k")
      (footprint "R0805")
      (description "RES SMD 100K OHM 1% 1/8W 0805")
      (fields
        (field (name "MANUFACTURER") "Yageo")
        (field (name "MANUFACTURER PART NUMBER") "RC0805FR-07100KL")
        (field (name ".CREATOR") "MM")
        (field (name ".CHECKED PCB") "RF")
        (field (name ".CHECKED SCH") "RF")
      )
      (libsource (lib "Integrated_Library_FEDEVEL_APR_2015") (part "RC0805FR-07100KL"))
    )
    (comp (ref "R2")
      (value "560R")
      (footprint "R0805")
      (description "RES SMD 560 OHM 1% 1/8W 0805")
      (fields
        (field (name "MANUFACTURER") "Yageo")
        (field (name "MANUFACTURER PART NUMBER") "RC0805FR-07560RL")
        (field (name ".CREATOR") "MM")
        (field (name ".CHECKED PCB") "RF")
        (field (name ".CHECKED SCH") "RF")
      )
      (libsource (lib "Integrated_Library_FEDEVEL_APR_2015") (part "RC0805FR-07560RL"))
    )
    (comp (ref "R3")
      (value "560R")
      (footprint "R0805")
      (description "RES SMD 560 OHM 1% 1/8W 0805")
      (fields
        (field (name "MANUFACTURER") "Yageo")
        (field (name "MANUFACTURER PART NUMBER") "RC0805FR-07560RL")
        (field (name ".CREATOR") "MM")
        (field (name ".CHECKED PCB") "RF")
        (field (name ".CHECKED SCH") "RF")
      )
      (libsource (lib "Integrated_Library_FEDEVEL_APR_2015") (part "RC0805FR-07560RL"))
    )
    (comp (ref "R4")
      (value "10k")
      (footprint "R0805")
      (description "RES SMD 10K OHM 1% 1/8W 0805")
      (fields
        (field (name "MANUFACTURER") "Yageo")
        (field (name "MANUFACTURER PART NUMBER") "RC0805FR-0710KL")
        (field (name ".CREATOR") "MM")
        (field (name ".CHECKED PCB") "RF")
        (field (name ".CHECKED SCH") "RF")
      )
      (libsource (lib "Integrated_Library_FEDEVEL_APR_2015") (part "RC0805FR-0710KL"))
    )
    (comp (ref "R5")
      (value "22R")
      (footprint "R0805")
      (description "RES SMD 22 OHM 1% 1/8W 0805")
      (fields
        (field (name "MANUFACTURER") "Yageo")
        (field (name "MANUFACTURER PART NUMBER") "RC0805FR-0722RL")
        (field (name ".CREATOR") "MM")
        (field (name ".CHECKED PCB") "RF")
        (field (name ".CHECKED SCH") "RF")
      )
      (libsource (lib "Integrated_Library_FEDEVEL_APR_2015") (part "RC0805FR-0722RL"))
    )
    (comp (ref "R6")
      (value "22R")
      (footprint "R0805")
      (description "RES SMD 22 OHM 1% 1/8W 0805")
      (fields
        (field (name "MANUFACTURER") "Yageo")
        (field (name "MANUFACTURER PART NUMBER") "RC0805FR-0722RL")
        (field (name ".CREATOR") "MM")
        (field (name ".CHECKED PCB") "RF")
        (field (name ".CHECKED SCH") "RF")
      )
      (libsource (lib "Integrated_Library_FEDEVEL_APR_2015") (part "RC0805FR-0722RL"))
    )
    (comp (ref "R7")
      (value "22R")
      (footprint "R0805")
      (description "RES SMD 22 OHM 1% 1/8W 0805")
      (fields
        (field (name "MANUFACTURER") "Yageo")
        (field (name "MANUFACTURER PART NUMBER") "RC0805FR-0722RL")
        (field (name ".CREATOR") "MM")
        (field (name ".CHECKED PCB") "RF")
        (field (name ".CHECKED SCH") "RF")
      )
      (libsource (lib "Integrated_Library_FEDEVEL_APR_2015") (part "RC0805FR-0722RL"))
    )
    (comp (ref "R8")
      (value "0R")
      (footprint "R0805")
      (description "RES 0.0 OHM 1/8W 0805 SMD")
      (fields
        (field (name "MANUFACTURER") "Yageo")
        (field (name "MANUFACTURER PART NUMBER") "RC0805JR-070RL")
        (field (name ".CHECKED PCB") "RF")
        (field (name ".CHECKED SCH") "RF")
      )
      (libsource (lib "Integrated_Library_FEDEVEL_APR_2015") (part "RC0805JR-070RL"))
    )
    (comp (ref "R9")
      (value "1M")
      (footprint "R0805")
      (description "RES SMD 1M OHM 1% 1/8W 0805")
      (fields
        (field (name "MANUFACTURER") "Yageo")
        (field (name "MANUFACTURER PART NUMBER") "RC0805FR-071ML")
        (field (name ".CREATOR") "MM")
        (field (name ".CHECKED PCB") "RF")
        (field (name ".CHECKED SCH") "RF")
      )
      (libsource (lib "Integrated_Library_FEDEVEL_APR_2015") (part "RC0805FR-071ML"))
    )
    (comp (ref "R10")
      (value "1k")
      (footprint "R0805")
      (description "RES SMD 1K OHM 1% 1/8W 0805")
      (fields
        (field (name "MANUFACTURER") "Yageo")
        (field (name "MANUFACTURER PART NUMBER") "RC0805FR-071KL")
        (field (name ".CREATOR") "MM")
        (field (name ".CHECKED PCB") "RF")
        (field (name ".CHECKED SCH") "RF")
      )
      (libsource (lib "Integrated_Library_FEDEVEL_APR_2015") (part "RC0805FR-071KL"))
    )
    (comp (ref "R11")
      (value "1k")
      (footprint "R0805")
      (description "RES SMD 1K OHM 1% 1/8W 0805")
      (fields
        (field (name "MANUFACTURER") "Yageo")
        (field (name "MANUFACTURER PART NUMBER") "RC0805FR-071KL")
        (field (name ".CREATOR") "MM")
        (field (name ".CHECKED PCB") "RF")
        (field (name ".CHECKED SCH") "RF")
      )
      (libsource (lib "Integrated_Library_FEDEVEL_APR_2015") (part "RC0805FR-071KL"))
    )
    (comp (ref "R12")
      (value "1k")
      (footprint "R0805")
      (description "RES SMD 1K OHM 1% 1/8W 0805")
      (fields
        (field (name "MANUFACTURER") "Yageo")
        (field (name "MANUFACTURER PART NUMBER") "RC0805FR-071KL")
        (field (name ".CREATOR") "MM")
        (field (name ".CHECKED PCB") "RF")
        (field (name ".CHECKED SCH") "RF")
      )
      (libsource (lib "Integrated_Library_FEDEVEL_APR_2015") (part "RC0805FR-071KL"))
    )
    (comp (ref "R13")
      (value "22R")
      (footprint "R0805")
      (description "RES SMD 22 OHM 1% 1/8W 0805")
      (fields
        (field (name "MANUFACTURER") "Yageo")
        (field (name "MANUFACTURER PART NUMBER") "RC0805FR-0722RL")
        (field (name ".CREATOR") "MM")
        (field (name ".CHECKED PCB") "RF")
        (field (name ".CHECKED SCH") "RF")
      )
      (libsource (lib "Integrated_Library_FEDEVEL_APR_2015") (part "RC0805FR-0722RL"))
    )
    (comp (ref "R14")
      (value "10k")
      (footprint "R0805")
      (description "RES SMD 10K OHM 1% 1/8W 0805")
      (fields
        (field (name "MANUFACTURER") "Yageo")
        (field (name "MANUFACTURER PART NUMBER") "RC0805FR-0710KL")
        (field (name ".CREATOR") "MM")
        (field (name ".CHECKED PCB") "RF")
        (field (name ".CHECKED SCH") "RF")
      )
      (libsource (lib "Integrated_Library_FEDEVEL_APR_2015") (part "RC0805FR-0710KL"))
    )
    (comp (ref "R15")
      (value "560R")
      (footprint "R0805")
      (description "RES SMD 560 OHM 1% 1/8W 0805")
      (fields
        (field (name "MANUFACTURER") "Yageo")
        (field (name "MANUFACTURER PART NUMBER") "RC0805FR-07560RL")
        (field (name ".CREATOR") "MM")
        (field (name ".CHECKED PCB") "RF")
        (field (name ".CHECKED SCH") "RF")
      )
      (libsource (lib "Integrated_Library_FEDEVEL_APR_2015") (part "RC0805FR-07560RL"))
    )
    (comp (ref "R16")
      (value "1M")
      (footprint "R0805")
      (description "RES SMD 1M OHM 1% 1/8W 0805")
      (fields
        (field (name "MANUFACTURER") "Yageo")
        (field (name "MANUFACTURER PART NUMBER") "RC0805FR-071ML")
        (field (name ".CREATOR") "MM")
        (field (name ".CHECKED PCB") "RF")
        (field (name ".CHECKED SCH") "RF")
      )
      (libsource (lib "Integrated_Library_FEDEVEL_APR_2015") (part "RC0805FR-071ML"))
    )
    (comp (ref "R17")
      (value "560R")
      (footprint "R0805")
      (description "RES SMD 560 OHM 1% 1/8W 0805")
      (fields
        (field (name "MANUFACTURER") "Yageo")
        (field (name "MANUFACTURER PART NUMBER") "RC0805FR-07560RL")
        (field (name ".CREATOR") "MM")
        (field (name ".CHECKED PCB") "RF")
        (field (name ".CHECKED SCH") "RF")
      )
      (libsource (lib "Integrated_Library_FEDEVEL_APR_2015") (part "RC0805FR-07560RL"))
    )
    (comp (ref "R18")
      (value "10k")
      (footprint "R0805")
      (description "RES SMD 10K OHM 1% 1/8W 0805")
      (fields
        (field (name "MANUFACTURER") "Yageo")
        (field (name "MANUFACTURER PART NUMBER") "RC0805FR-0710KL")
        (field (name ".CREATOR") "MM")
        (field (name ".CHECKED PCB") "RF")
        (field (name ".CHECKED SCH") "RF")
      )
      (libsource (lib "Integrated_Library_FEDEVEL_APR_2015") (part "RC0805FR-0710KL"))
    )
    (comp (ref "R19")
      (value "10k")
      (footprint "R0805")
      (description "RES SMD 10K OHM 1% 1/8W 0805")
      (fields
        (field (name "MANUFACTURER") "Yageo")
        (field (name "MANUFACTURER PART NUMBER") "RC0805FR-0710KL")
        (field (name ".CREATOR") "MM")
        (field (name ".CHECKED PCB") "RF")
        (field (name ".CHECKED SCH") "RF")
      )
      (libsource (lib "Integrated_Library_FEDEVEL_APR_2015") (part "RC0805FR-0710KL"))
    )
    (comp (ref "R20")
      (value "10k")
      (footprint "R0805")
      (description "RES SMD 10K OHM 1% 1/8W 0805")
      (fields
        (field (name "MANUFACTURER") "Yageo")
        (field (name "MANUFACTURER PART NUMBER") "RC0805FR-0710KL")
        (field (name ".CREATOR") "MM")
        (field (name ".CHECKED PCB") "RF")
        (field (name ".CHECKED SCH") "RF")
      )
      (libsource (lib "Integrated_Library_FEDEVEL_APR_2015") (part "RC0805FR-0710KL"))
    )
    (comp (ref "R21")
      (value "10k")
      (footprint "R0805")
      (description "RES SMD 10K OHM 1% 1/8W 0805")
      (fields
        (field (name "MANUFACTURER") "Yageo")
        (field (name "MANUFACTURER PART NUMBER") "RC0805FR-0710KL")
        (field (name ".CREATOR") "MM")
        (field (name ".CHECKED PCB") "RF")
        (field (name ".CHECKED SCH") "RF")
      )
      (libsource (lib "Integrated_Library_FEDEVEL_APR_2015") (part "RC0805FR-0710KL"))
    )
    (comp (ref "R22")
      (value "560R")
      (footprint "R0805")
      (description "RES SMD 560 OHM 1% 1/8W 0805")
      (fields
        (field (name "MANUFACTURER") "Yageo")
        (field (name "MANUFACTURER PART NUMBER") "RC0805FR-07560RL")
        (field (name ".CREATOR") "MM")
        (field (name ".CHECKED PCB") "RF")
        (field (name ".CHECKED SCH") "RF")
      )
      (libsource (lib "Integrated_Library_FEDEVEL_APR_2015") (part "RC0805FR-07560RL"))
    )
    (comp (ref "R23")
      (value "22R")
      (footprint "R0805")
      (description "RES SMD 22 OHM 1% 1/8W 0805")
      (fields
        (field (name "MANUFACTURER") "Yageo")
        (field (name "MANUFACTURER PART NUMBER") "RC0805FR-0722RL")
        (field (name ".CREATOR") "MM")
        (field (name ".CHECKED PCB") "RF")
        (field (name ".CHECKED SCH") "RF")
      )
      (libsource (lib "Integrated_Library_FEDEVEL_APR_2015") (part "RC0805FR-0722RL"))
    )
    (comp (ref "R24")
      (value "22R")
      (footprint "R0805")
      (description "RES SMD 22 OHM 1% 1/8W 0805")
      (fields
        (field (name "MANUFACTURER") "Yageo")
        (field (name "MANUFACTURER PART NUMBER") "RC0805FR-0722RL")
        (field (name ".CREATOR") "MM")
        (field (name ".CHECKED PCB") "RF")
        (field (name ".CHECKED SCH") "RF")
      )
      (libsource (lib "Integrated_Library_FEDEVEL_APR_2015") (part "RC0805FR-0722RL"))
    )
    (comp (ref "R25")
      (value "22R")
      (footprint "R0805")
      (description "RES SMD 22 OHM 1% 1/8W 0805")
      (fields
        (field (name "MANUFACTURER") "Yageo")
        (field (name "MANUFACTURER PART NUMBER") "RC0805FR-0722RL")
        (field (name ".CREATOR") "MM")
        (field (name ".CHECKED PCB") "RF")
        (field (name ".CHECKED SCH") "RF")
      )
      (libsource (lib "Integrated_Library_FEDEVEL_APR_2015") (part "RC0805FR-0722RL"))
    )
    (comp (ref "R26")
      (value "0R")
      (footprint "R0805")
      (description "RES 0.0 OHM 1/8W 0805 SMD")
      (fields
        (field (name "MANUFACTURER") "Yageo")
        (field (name "MANUFACTURER PART NUMBER") "RC0805JR-070RL")
        (field (name ".CHECKED PCB") "RF")
        (field (name ".CHECKED SCH") "RF")
      )
      (libsource (lib "Integrated_Library_FEDEVEL_APR_2015") (part "RC0805JR-070RL"))
    )
    (comp (ref "R27")
      (value "0R")
      (footprint "R0805")
      (description "RES 0.0 OHM 1/8W 0805 SMD")
      (fields
        (field (name "MANUFACTURER") "Yageo")
        (field (name "MANUFACTURER PART NUMBER") "RC0805JR-070RL")
        (field (name ".CHECKED PCB") "RF")
        (field (name ".CHECKED SCH") "RF")
      )
      (libsource (lib "Integrated_Library_FEDEVEL_APR_2015") (part "RC0805JR-070RL"))
    )
    (comp (ref "R28")
      (value "0R")
      (footprint "R0805")
      (description "RES 0.0 OHM 1/8W 0805 SMD")
      (fields
        (field (name "MANUFACTURER") "Yageo")
        (field (name "MANUFACTURER PART NUMBER") "RC0805JR-070RL")
        (field (name ".CHECKED PCB") "RF")
        (field (name ".CHECKED SCH") "RF")
      )
      (libsource (lib "Integrated_Library_FEDEVEL_APR_2015") (part "RC0805JR-070RL"))
    )
    (comp (ref "SCKT FOR U1")
      (value "28-DIP Socket")
      (footprint "28_DIP_7.62mm_SOCKET")
      (description "CONN IC DIP SOCKET 28POS TIN")
      (fields
        (field (name "MANUFACTURER") "3M")
        (field (name "MANUFACTURER PART NUMBER") "4828-3004-CP")
        (field (name ".CREATOR") "MM")
        (field (name ".CHECKED PCB") "RF")
        (field (name ".CHECKED SCH") "RF")
      )
      (libsource (lib "Integrated_Library_FEDEVEL_APR_2015") (part "4828-3004-CP"))
    )
    (comp (ref "SW1")
      (value "1825910-6")
      (footprint "1825910-6")
      (description "SWITCH TACTILE SPST-NO 0.05A 24V")
      (fields
        (field (name "MANUFACTURER") "TE Connectivity")
        (field (name ".CREATOR") "MM")
        (field (name ".CHECKED PCB") "RF")
        (field (name ".CHECKED SCH") "RF")
      )
      (libsource (lib "Integrated_Library_FEDEVEL_APR_2015") (part "1825910-6"))
    )
    (comp (ref "SW2")
      (value "1825910-6")
      (footprint "1825910-6")
      (description "SWITCH TACTILE SPST-NO 0.05A 24V")
      (fields
        (field (name "MANUFACTURER") "TE Connectivity")
        (field (name ".CREATOR") "MM")
        (field (name ".CHECKED PCB") "RF")
        (field (name ".CHECKED SCH") "RF")
      )
      (libsource (lib "Integrated_Library_FEDEVEL_APR_2015") (part "1825910-6"))
    )
    (comp (ref "U1")
      (value "ATMEGA328P-PU")
      (footprint "28_DIP_7.62mm")
      (description "IC MCU 8BIT 32KB FLASH 28DIP")
      (fields
        (field (name "MANUFACTURER") "Atmel")
        (field (name ".CREATOR") "MM")
        (field (name ".CHECKED PCB") "RF")
        (field (name ".CHECKED SCH") "RF")
      )
      (libsource (lib "Integrated_Library_FEDEVEL_APR_2015") (part "ATMEGA328P-PU"))
    )
    (comp (ref "U2")
      (value "ATMEGA16U2-AU")
      (footprint "TQFP32")
      (description "IC MCU 8BIT 16KB FLASH 32TQFP")
      (fields
        (field (name "MANUFACTURER") "Atmel")
        (field (name ".CREATOR") "MM")
        (field (name ".CHECKED PCB") "RF")
        (field (name ".CHECKED SCH") "RF")
      )
      (libsource (lib "Integrated_Library_FEDEVEL_APR_2015") (part "ATMEGA16U2-AU"))
    )
    (comp (ref "U3")
      (value "TL1963A-33DCQR")
      (footprint "DCQ (R-PDSO-G6)")
      (description "IC REG LDO 3.3V 1.5A SOT223-6")
      (fields
        (field (name "MANUFACTURER") "Texas Instruments")
        (field (name ".CREATOR") "MM")
        (field (name ".CHECKED PCB") "RF")
        (field (name ".CHECKED SCH") "RF")
      )
      (libsource (lib "Integrated_Library_FEDEVEL_APR_2015") (part "TL1963A-33DCQR"))
    )
    (comp (ref "U4")
      (value "SN74AHC1G09DBVR")
      (footprint "DBV_SOT_23_5")
      (description "IC GATE AND SGL 2INP SOT23-5")
      (fields (field (name "MANUFACTURER") "Texas Instruments") (field (name ".CREATOR") "MM"))
      (libsource (lib "Integrated_Library_FEDEVEL_APR_2015") (part "SN74AHC1G09DBVR"))
    )
    (comp (ref "U5")
      (value "SN74AHC1G09DBVR")
      (footprint "DBV_SOT_23_5")
      (description "IC GATE AND SGL 2INP SOT23-5")
      (fields (field (name "MANUFACTURER") "Texas Instruments") (field (name ".CREATOR") "MM"))
      (libsource (lib "Integrated_Library_FEDEVEL_APR_2015") (part "SN74AHC1G09DBVR"))
    )
    (comp (ref "U6")
      (value "SN74AHC1G09DBVR")
      (footprint "DBV_SOT_23_5")
      (description "IC GATE AND SGL 2INP SOT23-5")
      (fields (field (name "MANUFACTURER") "Texas Instruments") (field (name ".CREATOR") "MM"))
      (libsource (lib "Integrated_Library_FEDEVEL_APR_2015") (part "SN74AHC1G09DBVR"))
    )
    (comp (ref "U7")
      (value "SN74AHC1G09DBVR")
      (footprint "DBV_SOT_23_5")
      (description "IC GATE AND SGL 2INP SOT23-5")
      (fields (field (name "MANUFACTURER") "Texas Instruments") (field (name ".CREATOR") "MM"))
      (libsource (lib "Integrated_Library_FEDEVEL_APR_2015") (part "SN74AHC1G09DBVR"))
    )
    (comp (ref "Y1")
      (value "ABM7-16.000MHZ-D2Y-T")
      (footprint "ABM7_v1_1_BIG")
      (description "CRYSTAL 16MHZ 18PF SMD")
      (fields
        (field (name "MANUFACTURER") "Abracon LLC")
        (field (name ".CREATOR") "MM")
        (field (name ".CHECKED PCB") "RF")
        (field (name ".CHECKED SCH") "RF")
      )
      (libsource (lib "Integrated_Library_FEDEVEL_APR_2015") (part "ABM7-16.000MHZ-D2Y-T"))
    )
    (comp (ref "Y2")
      (value "ABM7-16.000MHZ-D2Y-T")
      (footprint "ABM7_v1_1_BIG")
      (description "CRYSTAL 16MHZ 18PF SMD")
      (fields
        (field (name "MANUFACTURER") "Abracon LLC")
        (field (name ".CREATOR") "MM")
        (field (name ".CHECKED PCB") "RF")
        (field (name ".CHECKED SCH") "RF")
      )
      (libsource (lib "Integrated_Library_FEDEVEL_APR_2015") (part "ABM7-16.000MHZ-D2Y-T"))
    )
    (comp (ref "Z1")
      (value "CG0603MLC-05E")
      (footprint "R0603")
      (description "VARISTOR 0603")
      (fields
        (field (name "MANUFACTURER") "Bourns Inc.")
        (field (name ".CREATOR") "MM")
        (field (name ".CHECKED PCB") "RF")
        (field (name ".CHECKED SCH") "RF")
      )
      (libsource (lib "Integrated_Library_FEDEVEL_APR_2015") (part "CG0603MLC-05E"))
    )
    (comp (ref "Z2")
      (value "CG0603MLC-05E")
      (footprint "R0603")
      (description "VARISTOR 0603")
      (fields
        (field (name "MANUFACTURER") "Bourns Inc.")
        (field (name ".CREATOR") "MM")
        (field (name ".CHECKED PCB") "RF")
        (field (name ".CHECKED SCH") "RF")
      )
      (libsource (lib "Integrated_Library_FEDEVEL_APR_2015") (part "CG0603MLC-05E"))
    )
  )
  (nets
    (net (code "1") (name "+3V3") (class "Default")
      (node (ref "C13") (pin "1") (pinfunction "1_1") (pintype "passive"))
      (node (ref "C16") (pin "1") (pinfunction "1_1") (pintype "passive"))
      (node (ref "J1") (pin "4") (pinfunction "4_4") (pintype "passive"))
      (node (ref "JP4") (pin "3") (pinfunction "3_3") (pintype "passive"))
      (node (ref "R28") (pin "1") (pinfunction "1_1") (pintype "passive"))
      (node (ref "U3") (pin "4") (pinfunction "OUT_4") (pintype "passive"))
      (node (ref "U3") (pin "5") (pinfunction "SENSE_5") (pintype "passive"))
    )
    (net (code "2") (name "+5V") (class "Default")
      (node (ref "C12") (pin "1") (pinfunction "1_1") (pintype "passive"))
      (node (ref "C14") (pin "1") (pinfunction "1_1") (pintype "passive"))
      (node (ref "C2") (pin "1") (pinfunction "1_1") (pintype "passive"))
      (node (ref "C6") (pin "1") (pinfunction "1_1") (pintype "passive"))
      (node (ref "J1") (pin "5") (pinfunction "5_5") (pintype "passive"))
      (node (ref "J8") (pin "1") (pinfunction "1_1") (pintype "passive"))
      (node (ref "JP4") (pin "1") (pinfunction "1_1") (pintype "passive"))
      (node (ref "L1") (pin "2") (pinfunction "2_2") (pintype "passive"))
      (node (ref "R27") (pin "2") (pinfunction "2_2") (pintype "passive"))
      (node (ref "U2") (pin "31") (pinfunction "UVCC_31") (pintype "passive"))
      (node (ref "U3") (pin "1") (pinfunction "~{SHDN}_1") (pintype "passive"))
      (node (ref "U3") (pin "2") (pinfunction "IN_2") (pintype "passive"))
    )
    (net (code "3") (name "+5V{slash}3V3") (class "Default")
      (node (ref "C15") (pin "1") (pinfunction "1_1") (pintype "passive"))
      (node (ref "C17") (pin "1") (pinfunction "1_1") (pintype "passive"))
      (node (ref "C26") (pin "1") (pinfunction "1_1") (pintype "passive"))
      (node (ref "C28") (pin "1") (pinfunction "1_1") (pintype "passive"))
      (node (ref "C29") (pin "1") (pinfunction "1_1") (pintype "passive"))
      (node (ref "C30") (pin "1") (pinfunction "1_1") (pintype "passive"))
      (node (ref "C34") (pin "1") (pinfunction "1_1") (pintype "passive"))
      (node (ref "C8") (pin "1") (pinfunction "1_1") (pintype "passive"))
      (node (ref "D5") (pin "1") (pinfunction "Cathode_1") (pintype "passive"))
      (node (ref "D6") (pin "1") (pinfunction "Cathode_1") (pintype "passive"))
      (node (ref "FB1") (pin "1") (pinfunction "1_1") (pintype "passive"))
      (node (ref "FB2") (pin "1") (pinfunction "1_1") (pintype "passive"))
      (node (ref "FB3") (pin "1") (pinfunction "1_1") (pintype "passive"))
      (node (ref "J1") (pin "2") (pinfunction "2_2") (pintype "passive"))
      (node (ref "J5") (pin "2") (pinfunction "2_2") (pintype "passive"))
      (node (ref "J6") (pin "2") (pinfunction "2_2") (pintype "passive"))
      (node (ref "JP4") (pin "2") (pinfunction "2_2") (pintype "passive"))
      (node (ref "R1") (pin "2") (pinfunction "2_2") (pintype "passive"))
      (node (ref "R14") (pin "2") (pinfunction "2_2") (pintype "passive"))
      (node (ref "R15") (pin "2") (pinfunction "2_2") (pintype "passive"))
      (node (ref "R17") (pin "2") (pinfunction "2_2") (pintype "passive"))
      (node (ref "R18") (pin "2") (pinfunction "2_2") (pintype "passive"))
      (node (ref "R19") (pin "2") (pinfunction "2_2") (pintype "passive"))
      (node (ref "R2") (pin "2") (pinfunction "2_2") (pintype "passive"))
      (node (ref "R20") (pin "2") (pinfunction "2_2") (pintype "passive"))
      (node (ref "R21") (pin "2") (pinfunction "2_2") (pintype "passive"))
      (node (ref "R27") (pin "1") (pinfunction "1_1") (pintype "passive"))
      (node (ref "R28") (pin "2") (pinfunction "2_2") (pintype "passive"))
      (node (ref "R3") (pin "2") (pinfunction "2_2") (pintype "passive"))
      (node (ref "R4") (pin "2") (pinfunction "2_2") (pintype "passive"))
      (node (ref "U4") (pin "5") (pinfunction "VCC_5") (pintype "power_in"))
      (node (ref "U5") (pin "5") (pinfunction "VCC_5") (pintype "power_in"))
      (node (ref "U6") (pin "5") (pinfunction "VCC_5") (pintype "power_in"))
      (node (ref "U7") (pin "5") (pinfunction "VCC_5") (pintype "power_in"))
    )
    (net (code "4") (name "+AREF") (class "Default")
      (node (ref "C21") (pin "1") (pinfunction "1_1") (pintype "passive"))
      (node (ref "C24") (pin "1") (pinfunction "1_1") (pintype "passive"))
      (node (ref "J4") (pin "8") (pinfunction "8_8") (pintype "passive"))
      (node (ref "U1") (pin "21") (pinfunction "AREF_21") (pintype "passive"))
    )
    (net (code "5") (name "/+3V3_16U2_UCAP") (class "Default")
      (node (ref "C7") (pin "2") (pinfunction "2_2") (pintype "passive"))
      (node (ref "R26") (pin "1") (pinfunction "1_1") (pintype "passive"))
      (node (ref "U2") (pin "27") (pinfunction "UCAP_27") (pintype "passive"))
    )
    (net (code "6") (name "/+5V_USB") (class "Default")
      (node (ref "C1") (pin "1") (pinfunction "1_1") (pintype "passive"))
      (node (ref "J7") (pin "1") (pinfunction "P1_1") (pintype "passive"))
      (node (ref "L1") (pin "1") (pinfunction "1_1") (pintype "passive"))
    )
    (net (code "7") (name "/+5V{slash}3V3_16U2") (class "Default")
      (node (ref "C5") (pin "1") (pinfunction "1_1") (pintype "passive"))
      (node (ref "FB1") (pin "2") (pinfunction "2_2") (pintype "passive"))
      (node (ref "R26") (pin "2") (pinfunction "2_2") (pintype "passive"))
      (node (ref "U2") (pin "32") (pinfunction "AVCC_32") (pintype "passive"))
      (node (ref "U2") (pin "4") (pinfunction "VCC_4") (pintype "passive"))
    )
    (net (code "8") (name "/+5V{slash}3V3_328P_AVCC") (class "Default")
      (node (ref "C22") (pin "1") (pinfunction "1_1") (pintype "passive"))
      (node (ref "C23") (pin "1") (pinfunction "1_1") (pintype "passive"))
      (node (ref "FB3") (pin "2") (pinfunction "2_2") (pintype "passive"))
      (node (ref "U1") (pin "20") (pinfunction "AVCC_20") (pintype "passive"))
    )
    (net (code "9") (name "/+5V{slash}3V3_328P_VCC") (class "Default")
      (node (ref "C19") (pin "1") (pinfunction "1_1") (pintype "passive"))
      (node (ref "C20") (pin "1") (pinfunction "1_1") (pintype "passive"))
      (node (ref "FB2") (pin "2") (pinfunction "2_2") (pintype "passive"))
      (node (ref "U1") (pin "7") (pinfunction "VCC_7") (pintype "passive"))
    )
    (net (code "10") (name "/16U2PROG_328P_RESETn") (class "Default")
      (node (ref "JP1") (pin "2") (pinfunction "2_2") (pintype "passive"))
      (node (ref "R1") (pin "1") (pinfunction "1_1") (pintype "passive"))
      (node (ref "U2") (pin "13") (pinfunction "~{CTS}_/~{_HWB}_/_T0_/_AIN6_/_INT7_/_PD7_13") (pintype "passive"))
    )
    (net (code "11") (name "/16U2_16MHZ_XTAL1") (class "Default")
      (node (ref "C10") (pin "2") (pinfunction "2_2") (pintype "passive"))
      (node (ref "R9") (pin "1") (pinfunction "1_1") (pintype "passive"))
      (node (ref "U2") (pin "1") (pinfunction "XTAL1_1") (pintype "passive"))
      (node (ref "Y2") (pin "1") (pinfunction "1_1") (pintype "passive"))
    )
    (net (code "12") (name "/16U2_16MHZ_XTAL2") (class "Default")
      (node (ref "C9") (pin "2") (pinfunction "2_2") (pintype "passive"))
      (node (ref "R9") (pin "2") (pinfunction "2_2") (pintype "passive"))
      (node (ref "U2") (pin "2") (pinfunction "XTAL2_/_PC0_2") (pintype "passive"))
      (node (ref "Y2") (pin "2") (pinfunction "2_2") (pintype "passive"))
    )
    (net (code "13") (name "/16U2_BUF_RESETn") (class "Default")
      (node (ref "C31") (pin "1") (pinfunction "1_1") (pintype "passive"))
      (node (ref "R23") (pin "2") (pinfunction "2_2") (pintype "passive"))
      (node (ref "U5") (pin "1") (pinfunction "A_1") (pintype "passive"))
      (node (ref "U5") (pin "2") (pinfunction "B_2") (pintype "passive"))
    )
    (net (code "14") (name "/16U2_HDR_RESETn") (class "Default")
      (node (ref "J6") (pin "5") (pinfunction "5_5") (pintype "passive"))
      (node (ref "JP3") (pin "3") (pinfunction "3_3") (pintype "passive"))
    )
    (net (code "15") (name "/16U2_MISO") (class "Default")
      (node (ref "J6") (pin "1") (pinfunction "1_1") (pintype "passive"))
      (node (ref "U2") (pin "17") (pinfunction "PDO_/_MISO_/_PCINT3_/_PB3_17") (pintype "passive"))
    )
    (net (code "16") (name "/16U2_MOSI") (class "Default")
      (node (ref "J6") (pin "4") (pinfunction "4_4") (pintype "passive"))
      (node (ref "U2") (pin "16") (pinfunction "PDI_/_MOSI_/_PCINT2_/_PB2_16") (pintype "passive"))
    )
    (net (code "17") (name "/16U2_PB4") (class "Default")
      (node (ref "JP2") (pin "1") (pinfunction "1_1") (pintype "passive"))
      (node (ref "JP3") (pin "2") (pinfunction "2_2") (pintype "passive"))
      (node (ref "U2") (pin "18") (pinfunction "T1_/_PCINT4_/_PB4_18") (pintype "passive"))
    )
    (net (code "18") (name "/16U2_PB5") (class "Default")
      (node (ref "JP2") (pin "3") (pinfunction "3_3") (pintype "passive"))
      (node (ref "U2") (pin "19") (pinfunction "PCINT5_/_PB5_19") (pintype "passive"))
    )
    (net (code "19") (name "/16U2_PB6") (class "Default")
      (node (ref "JP2") (pin "2") (pinfunction "2_2") (pintype "passive"))
      (node (ref "U2") (pin "20") (pinfunction "PCINT6_/_PB6_20") (pintype "passive"))
    )
    (net (code "20") (name "/16U2_PB7") (class "Default")
      (node (ref "JP2") (pin "4") (pinfunction "4_4") (pintype "passive"))
      (node (ref "U2") (pin "21") (pinfunction "OC.0A_/_OC.1C_/_PCINT7_/_PB7_21") (pintype "passive"))
    )
    (net (code "21") (name "/16U2_RESETn") (class "Default")
      (node (ref "JP3") (pin "4") (pinfunction "4_4") (pintype "passive"))
      (node (ref "R4") (pin "1") (pinfunction "1_1") (pintype "passive"))
      (node (ref "U2") (pin "24") (pinfunction "PC1_/~{_RESET}_/_DW_24") (pintype "passive"))
      (node (ref "U5") (pin "4") (pinfunction "Y_4") (pintype "passive"))
    )
    (net (code "22") (name "/16U2_RXD") (class "Default")
      (node (ref "R11") (pin "1") (pinfunction "1_1") (pintype "passive"))
      (node (ref "U2") (pin "8") (pinfunction "RXD1_/_AIN1_/_INT2_/_PD2_8") (pintype "passive"))
    )
    (net (code "23") (name "/16U2_RX_LED") (class "Default")
      (node (ref "D4") (pin "1") (pinfunction "cathode_1") (pintype "passive"))
      (node (ref "U2") (pin "10") (pinfunction "AIN3_/_INT5_/_PD4_10") (pintype "passive"))
    )
    (net (code "24") (name "/16U2_SCLK") (class "Default")
      (node (ref "J6") (pin "3") (pinfunction "3_3") (pintype "passive"))
      (node (ref "R5") (pin "2") (pinfunction "2_2") (pintype "passive"))
    )
    (net (code "25") (name "/16U2_SCLK_R") (class "Default")
      (node (ref "R5") (pin "1") (pinfunction "1_1") (pintype "passive"))
      (node (ref "U2") (pin "15") (pinfunction "SCLK_/_PCINT1_/_PB1_15") (pintype "passive"))
    )
    (net (code "26") (name "/16U2_TXD") (class "Default")
      (node (ref "R10") (pin "1") (pinfunction "1_1") (pintype "passive"))
      (node (ref "U2") (pin "9") (pinfunction "TXD1_/_INT3_/_PD3_9") (pintype "passive"))
    )
    (net (code "27") (name "/16U2_TX_LED") (class "Default")
      (node (ref "D3") (pin "1") (pinfunction "cathode_1") (pintype "passive"))
      (node (ref "U2") (pin "11") (pinfunction "XCK_/_AIN4_/_PCINT12_/_PD5_11") (pintype "passive"))
    )
    (net (code "28") (name "/328P_16MHZ_XTAL1") (class "Default")
      (node (ref "C27") (pin "2") (pinfunction "2_2") (pintype "passive"))
      (node (ref "R16") (pin "1") (pinfunction "1_1") (pintype "passive"))
      (node (ref "U1") (pin "9") (pinfunction "PB6_/_PCINT6_/_TOSC1_/_XTAL1_9") (pintype "passive"))
      (node (ref "Y1") (pin "1") (pinfunction "1_1") (pintype "passive"))
    )
    (net (code "29") (name "/328P_16MHZ_XTAL2") (class "Default")
      (node (ref "C25") (pin "2") (pinfunction "2_2") (pintype "passive"))
      (node (ref "R16") (pin "2") (pinfunction "2_2") (pintype "passive"))
      (node (ref "U1") (pin "10") (pinfunction "PB7_/_PCINT7_/_TOSC2_/_XTAL2_10") (pintype "passive"))
      (node (ref "Y1") (pin "2") (pinfunction "2_2") (pintype "passive"))
    )
    (net (code "30") (name "/328P_AUTORESETn") (class "Default")
      (node (ref "C11") (pin "1") (pinfunction "1_1") (pintype "passive"))
      (node (ref "R18") (pin "1") (pinfunction "1_1") (pintype "passive"))
      (node (ref "U6") (pin "1") (pinfunction "A_1") (pintype "passive"))
    )
    (net (code "31") (name "/328P_BUF_RESETn") (class "Default")
      (node (ref "C32") (pin "1") (pinfunction "1_1") (pintype "passive"))
      (node (ref "R24") (pin "2") (pinfunction "2_2") (pintype "passive"))
      (node (ref "U6") (pin "2") (pinfunction "B_2") (pintype "passive"))
    )
    (net (code "32") (name "/328P_RESETn") (class "Default")
      (node (ref "J1") (pin "3") (pinfunction "3_3") (pintype "passive"))
      (node (ref "J5") (pin "5") (pinfunction "5_5") (pintype "passive"))
      (node (ref "JP3") (pin "1") (pinfunction "1_1") (pintype "passive"))
      (node (ref "R14") (pin "1") (pinfunction "1_1") (pintype "passive"))
      (node (ref "U1") (pin "1") (pinfunction "PC6_/_PCINT14_/~{_RESET}_1") (pintype "passive"))
      (node (ref "U6") (pin "4") (pinfunction "Y_4") (pintype "passive"))
    )
    (net (code "33") (name "/AD0") (class "Default")
      (node (ref "J2") (pin "1") (pinfunction "1_1") (pintype "passive"))
      (node (ref "U1") (pin "23") (pinfunction "PCINT8_/_ADC0_/_PC0_23") (pintype "passive"))
    )
    (net (code "34") (name "/AD1") (class "Default")
      (node (ref "J2") (pin "2") (pinfunction "2_2") (pintype "passive"))
      (node (ref "U1") (pin "24") (pinfunction "PCINT9_/_ADC1_/_PC1_24") (pintype "passive"))
    )
    (net (code "35") (name "/AD2") (class "Default")
      (node (ref "J2") (pin "3") (pinfunction "3_3") (pintype "passive"))
      (node (ref "U1") (pin "25") (pinfunction "PCINT10_/_ADC2_/_PC2_25") (pintype "passive"))
    )
    (net (code "36") (name "/AD3") (class "Default")
      (node (ref "J2") (pin "4") (pinfunction "4_4") (pintype "passive"))
      (node (ref "U1") (pin "26") (pinfunction "PCINT11_/_ADC3_/_PC3_26") (pintype "passive"))
    )
    (net (code "37") (name "/AD4{slash}SDA") (class "Default")
      (node (ref "J2") (pin "5") (pinfunction "5_5") (pintype "passive"))
      (node (ref "J4") (pin "9") (pinfunction "9_9") (pintype "passive"))
      (node (ref "U1") (pin "27") (pinfunction "SDA_/_PCINT12_/_ADC4_/_PC4_27") (pintype "passive"))
    )
    (net (code "38") (name "/AD5{slash}SCL") (class "Default")
      (node (ref "J2") (pin "6") (pinfunction "6_6") (pintype "passive"))
      (node (ref "J4") (pin "10") (pinfunction "10_10") (pintype "passive"))
      (node (ref "U1") (pin "28") (pinfunction "SCL_/_PCINT13_/_ADC5_/_PC5_28") (pintype "passive"))
    )
    (net (code "39") (name "/BUTTON_RESETn") (class "Default")
      (node (ref "D6") (pin "2") (pinfunction "Anode_2") (pintype "passive"))
      (node (ref "R20") (pin "1") (pinfunction "1_1") (pintype "passive"))
      (node (ref "R24") (pin "1") (pinfunction "1_1") (pintype "passive"))
      (node (ref "SW1") (pin "1") (pinfunction "1_1") (pintype "passive"))
      (node (ref "SW1") (pin "2") (pinfunction "2_2") (pintype "passive"))
    )
    (net (code "40") (name "/CON_USB_N") (class "Default")
      (node (ref "J7") (pin "2") (pinfunction "P2_2") (pintype "passive"))
      (node (ref "R6") (pin "1") (pinfunction "1_1") (pintype "passive"))
      (node (ref "Z1") (pin "2") (pinfunction "2_2") (pintype "passive"))
    )
    (net (code "41") (name "/CON_USB_P") (class "Default")
      (node (ref "J7") (pin "3") (pinfunction "P3_3") (pintype "passive"))
      (node (ref "R7") (pin "1") (pinfunction "1_1") (pintype "passive"))
      (node (ref "Z2") (pin "2") (pinfunction "2_2") (pintype "passive"))
    )
    (net (code "42") (name "/IO0") (class "Default")
      (node (ref "J3") (pin "1") (pinfunction "1_1") (pintype "passive"))
      (node (ref "R10") (pin "2") (pinfunction "2_2") (pintype "passive"))
      (node (ref "U1") (pin "2") (pinfunction "RXD_/_PCINT16_/_PD0_2") (pintype "passive"))
    )
    (net (code "43") (name "/IO1") (class "Default")
      (node (ref "J3") (pin "2") (pinfunction "2_2") (pintype "passive"))
      (node (ref "R11") (pin "2") (pinfunction "2_2") (pintype "passive"))
      (node (ref "U1") (pin "3") (pinfunction "TXD_/_PCINT17_/_PD1_3") (pintype "passive"))
    )
    (net (code "44") (name "/IO2") (class "Default")
      (node (ref "J3") (pin "3") (pinfunction "3_3") (pintype "passive"))
      (node (ref "U1") (pin "4") (pinfunction "INT0_/_PCINT18_/_PD2_4") (pintype "passive"))
    )
    (net (code "45") (name "/IO3") (class "Default")
      (node (ref "J3") (pin "4") (pinfunction "4_4") (pintype "passive"))
      (node (ref "U1") (pin "5") (pinfunction "OC2B_/_INT1_/_PCINT19_/_PD3_5") (pintype "passive"))
    )
    (net (code "46") (name "/IO4") (class "Default")
      (node (ref "J3") (pin "5") (pinfunction "5_5") (pintype "passive"))
      (node (ref "U1") (pin "6") (pinfunction "XCK_/_T0_/_PCINT20_/_PD4_6") (pintype "passive"))
    )
    (net (code "47") (name "/IO5") (class "Default")
      (node (ref "J3") (pin "6") (pinfunction "6_6") (pintype "passive"))
      (node (ref "U1") (pin "11") (pinfunction "OC0B_/_T1_/_PCINT21_/_PD5_11") (pintype "passive"))
    )
    (net (code "48") (name "/IO6") (class "Default")
      (node (ref "J3") (pin "7") (pinfunction "7_7") (pintype "passive"))
      (node (ref "U1") (pin "12") (pinfunction "OC0A_/_AIN0_/_PCINT22_/_PD6_12") (pintype "passive"))
    )
    (net (code "49") (name "/IO7") (class "Default")
      (node (ref "J3") (pin "8") (pinfunction "8_8") (pintype "passive"))
      (node (ref "U1") (pin "13") (pinfunction "AIN1_/_PCINT23_/_PD7_13") (pintype "passive"))
    )
    (net (code "50") (name "/IO8") (class "Default")
      (node (ref "J4") (pin "1") (pinfunction "1_1") (pintype "passive"))
      (node (ref "R22") (pin "1") (pinfunction "1_1") (pintype "passive"))
      (node (ref "U1") (pin "14") (pinfunction "CLKO_/_ICP1_/_PCINT0_/_PB0_14") (pintype "passive"))
    )
    (net (code "51") (name "/IO9") (class "Default")
      (node (ref "J4") (pin "2") (pinfunction "2_2") (pintype "passive"))
      (node (ref "U1") (pin "15") (pinfunction "OC1A_/_PCINT1_/_PB1_15") (pintype "passive"))
    )
    (net (code "52") (name "/MISO") (class "Default")
      (node (ref "J4") (pin "5") (pinfunction "5_5") (pintype "passive"))
      (node (ref "J5") (pin "1") (pinfunction "1_1") (pintype "passive"))
      (node (ref "U1") (pin "18") (pinfunction "MISO_/_PCINT4_/_PB4_18") (pintype "passive"))
    )
    (net (code "53") (name "/MOSI") (class "Default")
      (node (ref "J4") (pin "4") (pinfunction "4_4") (pintype "passive"))
      (node (ref "J5") (pin "4") (pinfunction "4_4") (pintype "passive"))
      (node (ref "U1") (pin "17") (pinfunction "MOSI_/_OC2A_/_PCINT3_/_PB3_17") (pintype "passive"))
    )
    (net (code "54") (name "/SCK") (class "Default")
      (node (ref "J4") (pin "6") (pinfunction "6_6") (pintype "passive"))
      (node (ref "J5") (pin "3") (pinfunction "3_3") (pintype "passive"))
      (node (ref "R13") (pin "2") (pinfunction "2_2") (pintype "passive"))
      (node (ref "U4") (pin "1") (pinfunction "A_1") (pintype "passive"))
      (node (ref "U4") (pin "2") (pinfunction "B_2") (pintype "passive"))
    )
    (net (code "55") (name "/SCK_R") (class "Default")
      (node (ref "R13") (pin "1") (pinfunction "1_1") (pintype "passive"))
      (node (ref "U1") (pin "19") (pinfunction "SCK_/_PCINT5_/_PB5_19") (pintype "passive"))
    )
    (net (code "56") (name "/SS") (class "Default")
      (node (ref "J4") (pin "3") (pinfunction "3_3") (pintype "passive"))
      (node (ref "U1") (pin "16") (pinfunction "~{SS}_/_OC1B_/_PCINT2_/_PB2_16") (pintype "passive"))
    )
    (net (code "57") (name "/USB_N") (class "Default")
      (node (ref "R6") (pin "2") (pinfunction "2_2") (pintype "passive"))
      (node (ref "U2") (pin "30") (pinfunction "D-_30") (pintype "passive"))
    )
    (net (code "58") (name "/USB_P") (class "Default")
      (node (ref "R7") (pin "2") (pinfunction "2_2") (pintype "passive"))
      (node (ref "U2") (pin "29") (pinfunction "D+_29") (pintype "passive"))
    )
    (net (code "59") (name "/USER_BUTTON") (class "Default")
      (node (ref "R21") (pin "1") (pinfunction "1_1") (pintype "passive"))
      (node (ref "R25") (pin "1") (pinfunction "1_1") (pintype "passive"))
      (node (ref "SW2") (pin "1") (pinfunction "1_1") (pintype "passive"))
      (node (ref "SW2") (pin "2") (pinfunction "2_2") (pintype "passive"))
    )
    (net (code "60") (name "/USER_BUTTON_BUF") (class "Default")
      (node (ref "C33") (pin "1") (pinfunction "1_1") (pintype "passive"))
      (node (ref "R25") (pin "2") (pinfunction "2_2") (pintype "passive"))
      (node (ref "U7") (pin "1") (pinfunction "A_1") (pintype "passive"))
      (node (ref "U7") (pin "2") (pinfunction "B_2") (pintype "passive"))
    )
    (net (code "61") (name "GND") (class "Default")
      (node (ref "C1") (pin "2") (pinfunction "2_2") (pintype "passive"))
      (node (ref "C10") (pin "1") (pinfunction "1_1") (pintype "passive"))
      (node (ref "C12") (pin "2") (pinfunction "2_2") (pintype "passive"))
      (node (ref "C13") (pin "2") (pinfunction "2_2") (pintype "passive"))
      (node (ref "C14") (pin "2") (pinfunction "2_2") (pintype "passive"))
      (node (ref "C15") (pin "2") (pinfunction "2_2") (pintype "passive"))
      (node (ref "C16") (pin "2") (pinfunction "2_2") (pintype "passive"))
      (node (ref "C17") (pin "2") (pinfunction "2_2") (pintype "passive"))
      (node (ref "C19") (pin "2") (pinfunction "2_2") (pintype "passive"))
      (node (ref "C2") (pin "2") (pinfunction "2_2") (pintype "passive"))
      (node (ref "C20") (pin "2") (pinfunction "2_2") (pintype "passive"))
      (node (ref "C21") (pin "2") (pinfunction "2_2") (pintype "passive"))
      (node (ref "C22") (pin "2") (pinfunction "2_2") (pintype "passive"))
      (node (ref "C23") (pin "2") (pinfunction "2_2") (pintype "passive"))
      (node (ref "C24") (pin "2") (pinfunction "2_2") (pintype "passive"))
      (node (ref "C25") (pin "1") (pinfunction "1_1") (pintype "passive"))
      (node (ref "C26") (pin "2") (pinfunction "2_2") (pintype "passive"))
      (node (ref "C27") (pin "1") (pinfunction "1_1") (pintype "passive"))
      (node (ref "C28") (pin "2") (pinfunction "2_2") (pintype "passive"))
      (node (ref "C29") (pin "2") (pinfunction "2_2") (pintype "passive"))
      (node (ref "C30") (pin "2") (pinfunction "2_2") (pintype "passive"))
      (node (ref "C31") (pin "2") (pinfunction "2_2") (pintype "passive"))
      (node (ref "C32") (pin "2") (pinfunction "2_2") (pintype "passive"))
      (node (ref "C33") (pin "2") (pinfunction "2_2") (pintype "passive"))
      (node (ref "C34") (pin "2") (pinfunction "2_2") (pintype "passive"))
      (node (ref "C5") (pin "2") (pinfunction "2_2") (pintype "passive"))
      (node (ref "C6") (pin "2") (pinfunction "2_2") (pintype "passive"))
      (node (ref "C7") (pin "1") (pinfunction "1_1") (pintype "passive"))
      (node (ref "C8") (pin "2") (pinfunction "2_2") (pintype "passive"))
      (node (ref "C9") (pin "1") (pinfunction "1_1") (pintype "passive"))
      (node (ref "D1") (pin "1") (pinfunction "cathode_1") (pintype "passive"))
      (node (ref "J1") (pin "6") (pinfunction "6_6") (pintype "passive"))
      (node (ref "J1") (pin "7") (pinfunction "7_7") (pintype "passive"))
      (node (ref "J4") (pin "7") (pinfunction "7_7") (pintype "passive"))
      (node (ref "J5") (pin "6") (pinfunction "6_6") (pintype "passive"))
      (node (ref "J6") (pin "6") (pinfunction "6_6") (pintype "passive"))
      (node (ref "J7") (pin "10") (pinfunction "10_10") (pintype "passive"))
      (node (ref "J7") (pin "11") (pinfunction "11_11") (pintype "passive"))
      (node (ref "J7") (pin "5") (pinfunction "P5_5") (pintype "passive"))
      (node (ref "J7") (pin "6") (pinfunction "6_6") (pintype "passive"))
      (node (ref "J7") (pin "7") (pinfunction "7_7") (pintype "passive"))
      (node (ref "J7") (pin "8") (pinfunction "8_8") (pintype "passive"))
      (node (ref "J7") (pin "9") (pinfunction "9_9") (pintype "passive"))
      (node (ref "J9") (pin "1") (pinfunction "1_1") (pintype "passive"))
      (node (ref "MH1") (pin "1") (pinfunction "1_1") (pintype "passive"))
      (node (ref "MH2") (pin "1") (pinfunction "1_1") (pintype "passive"))
      (node (ref "MH3") (pin "1") (pinfunction "1_1") (pintype "passive"))
      (node (ref "R12") (pin "2") (pinfunction "2_2") (pintype "passive"))
      (node (ref "R8") (pin "2") (pinfunction "2_2") (pintype "passive"))
      (node (ref "SW1") (pin "3") (pinfunction "MECH1_3") (pintype "passive"))
      (node (ref "SW1") (pin "4") (pinfunction "MECH2_4") (pintype "passive"))
      (node (ref "SW2") (pin "3") (pinfunction "MECH1_3") (pintype "passive"))
      (node (ref "SW2") (pin "4") (pinfunction "MECH2_4") (pintype "passive"))
      (node (ref "U1") (pin "22") (pinfunction "GND_2_22") (pintype "passive"))
      (node (ref "U1") (pin "8") (pinfunction "GND_1_8") (pintype "passive"))
      (node (ref "U2") (pin "28") (pinfunction "UGND_28") (pintype "passive"))
      (node (ref "U2") (pin "3") (pinfunction "GND_3") (pintype "passive"))
      (node (ref "U3") (pin "3") (pinfunction "GND_3") (pintype "passive"))
      (node (ref "U3") (pin "6") (pinfunction "EPAD_6") (pintype "passive"))
      (node (ref "U4") (pin "3") (pinfunction "GND_3") (pintype "power_in"))
      (node (ref "U5") (pin "3") (pinfunction "GND_3") (pintype "power_in"))
      (node (ref "U6") (pin "3") (pinfunction "GND_3") (pintype "power_in"))
      (node (ref "U7") (pin "3") (pinfunction "GND_3") (pintype "power_in"))
      (node (ref "Z1") (pin "1") (pinfunction "1_1") (pintype "passive"))
      (node (ref "Z2") (pin "1") (pinfunction "1_1") (pintype "passive"))
    )
    (net (code "62") (name "Net-(C11-Pad2)") (class "Default")
      (node (ref "C11") (pin "2") (pinfunction "2_2") (pintype "passive"))
      (node (ref "JP1") (pin "1") (pinfunction "1_1") (pintype "passive"))
    )
    (net (code "63") (name "Net-(D1-ANODE)") (class "Default")
      (node (ref "D1") (pin "2") (pinfunction "ANODE_2") (pintype "passive"))
      (node (ref "R17") (pin "1") (pinfunction "1_1") (pintype "passive"))
    )
    (net (code "64") (name "Net-(D2-ANODE)") (class "Default")
      (node (ref "D2") (pin "2") (pinfunction "ANODE_2") (pintype "passive"))
      (node (ref "R15") (pin "1") (pinfunction "1_1") (pintype "passive"))
    )
    (net (code "65") (name "Net-(D2-cathode)") (class "Default")
      (node (ref "D2") (pin "1") (pinfunction "cathode_1") (pintype "passive"))
      (node (ref "U4") (pin "4") (pinfunction "Y_4") (pintype "passive"))
    )
    (net (code "66") (name "Net-(D3-ANODE)") (class "Default")
      (node (ref "D3") (pin "2") (pinfunction "ANODE_2") (pintype "passive"))
      (node (ref "R2") (pin "1") (pinfunction "1_1") (pintype "passive"))
    )
    (net (code "67") (name "Net-(D4-ANODE)") (class "Default")
      (node (ref "D4") (pin "2") (pinfunction "ANODE_2") (pintype "passive"))
      (node (ref "R3") (pin "1") (pinfunction "1_1") (pintype "passive"))
    )
    (net (code "68") (name "Net-(D5-Anode)") (class "Default")
      (node (ref "D5") (pin "2") (pinfunction "Anode_2") (pintype "passive"))
      (node (ref "R19") (pin "1") (pinfunction "1_1") (pintype "passive"))
      (node (ref "R23") (pin "1") (pinfunction "1_1") (pintype "passive"))
    )
    (net (code "69") (name "Net-(J7-P4)") (class "Default")
      (node (ref "J7") (pin "4") (pinfunction "P4_4") (pintype "passive"))
      (node (ref "R8") (pin "1") (pinfunction "1_1") (pintype "passive"))
    )
    (net (code "70") (name "Net-(JP1-Pad3)") (class "Default")
      (node (ref "JP1") (pin "3") (pinfunction "3_3") (pintype "passive"))
      (node (ref "R12") (pin "1") (pinfunction "1_1") (pintype "passive"))
    )
    (net (code "71") (name "Net-(U7-Y)") (class "Default")
      (node (ref "R22") (pin "2") (pinfunction "2_2") (pintype "passive"))
      (node (ref "U7") (pin "4") (pinfunction "Y_4") (pintype "passive"))
    )
    (net (code "72") (name "unconnected-(J1-Pad1)") (class "Default")
      (node (ref "J1") (pin "1") (pinfunction "1_1") (pintype "passive+no_connect"))
    )
    (net (code "73") (name "unconnected-(J1-Pad8)") (class "Default")
      (node (ref "J1") (pin "8") (pinfunction "8_8") (pintype "passive+no_connect"))
    )
    (net (code "74") (name "unconnected-(MH4-Pad1)") (class "Default")
      (node (ref "MH4") (pin "1") (pinfunction "1_1") (pintype "passive+no_connect"))
    )
    (net (code "75") (name "unconnected-(U2-AIN0_{slash}_INT1_{slash}_PD1-Pad7)") (class "Default")
      (node (ref "U2") (pin "7") (pinfunction "AIN0_/_INT1_/_PD1_7") (pintype "passive+no_connect"))
    )
    (net (code "76") (name "unconnected-(U2-AIN2_{slash}_PCINT11_{slash}_PC2-Pad5)") (class "Default")
      (node (ref "U2") (pin "5") (pinfunction "AIN2_/_PCINT11_/_PC2_5") (pintype "passive+no_connect"))
    )
    (net (code "77") (name "unconnected-(U2-CLKO_{slash}_ICP1_{slash}_INT4_{slash}_PC7-Pad22)") (class "Default")
      (node (ref "U2") (pin "22") (pinfunction "CLKO_/_ICP1_/_INT4_/_PC7_22") (pintype "passive+no_connect"))
    )
    (net (code "78") (name "unconnected-(U2-OC.0B_{slash}_INT0_{slash}_PD0-Pad6)") (class "Default")
      (node (ref "U2") (pin "6") (pinfunction "OC.0B_/_INT0_/_PD0_6") (pintype "passive+no_connect"))
    )
    (net (code "79") (name "unconnected-(U2-OC.1A_{slash}_PCINT8_{slash}_PC6-Pad23)") (class "Default")
      (node (ref "U2") (pin "23") (pinfunction "OC.1A_/_PCINT8_/_PC6_23") (pintype "passive+no_connect"))
    )
    (net (code "80") (name "unconnected-(U2-OC.1B_{slash}_PCINT9_{slash}_PC5-Pad25)") (class "Default")
      (node (ref "U2") (pin "25") (pinfunction "OC.1B_/_PCINT9_/_PC5_25") (pintype "passive+no_connect"))
    )
    (net (code "81") (name "unconnected-(U2-PCINT10_{slash}_PC4-Pad26)") (class "Default")
      (node (ref "U2") (pin "26") (pinfunction "PCINT10_/_PC4_26") (pintype "passive+no_connect"))
    )
    (net (code "82") (name "unconnected-(U2-~{RTS}_{slash}_AIN5_{slash}_INT6_{slash}_PD6-Pad12)") (class "Default")
      (node (ref "U2") (pin "12") (pinfunction "~{RTS}_/_AIN5_/_INT6_/_PD6_12") (pintype "passive"))
    )
    (net (code "83") (name "unconnected-(U2-~{SS}_{slash}_PCINT0_{slash}_PB0-Pad14)") (class "Default")
      (node (ref "U2") (pin "14") (pinfunction "~{SS}_/_PCINT0_/_PB0_14") (pintype "passive+no_connect"))
    )
  )
)
